# EL1034v4.net
KiCad netlist of a schematic drawn in EAGLE
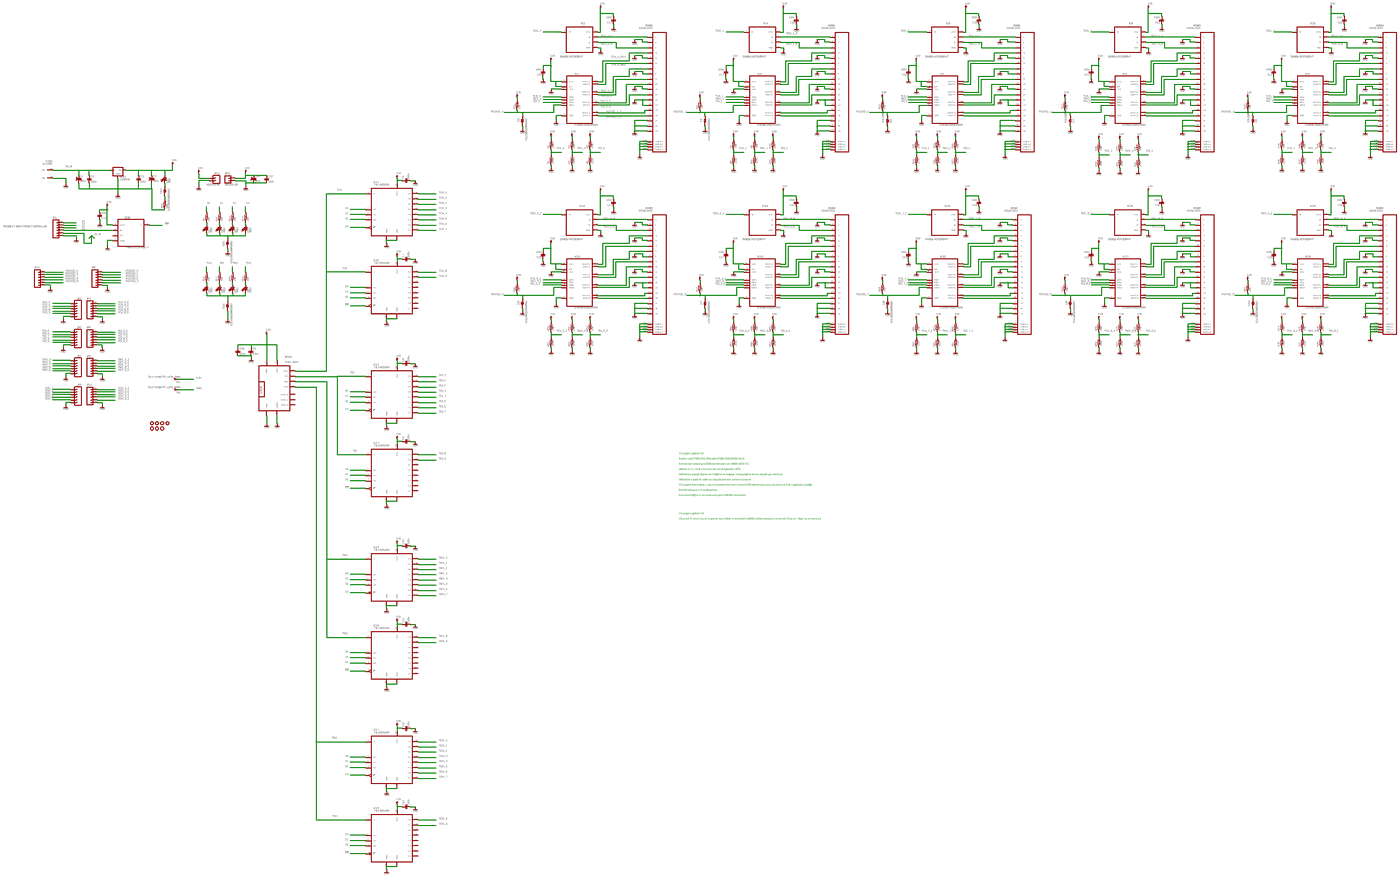
[diagram p0: schematic, sheet 1, overview]
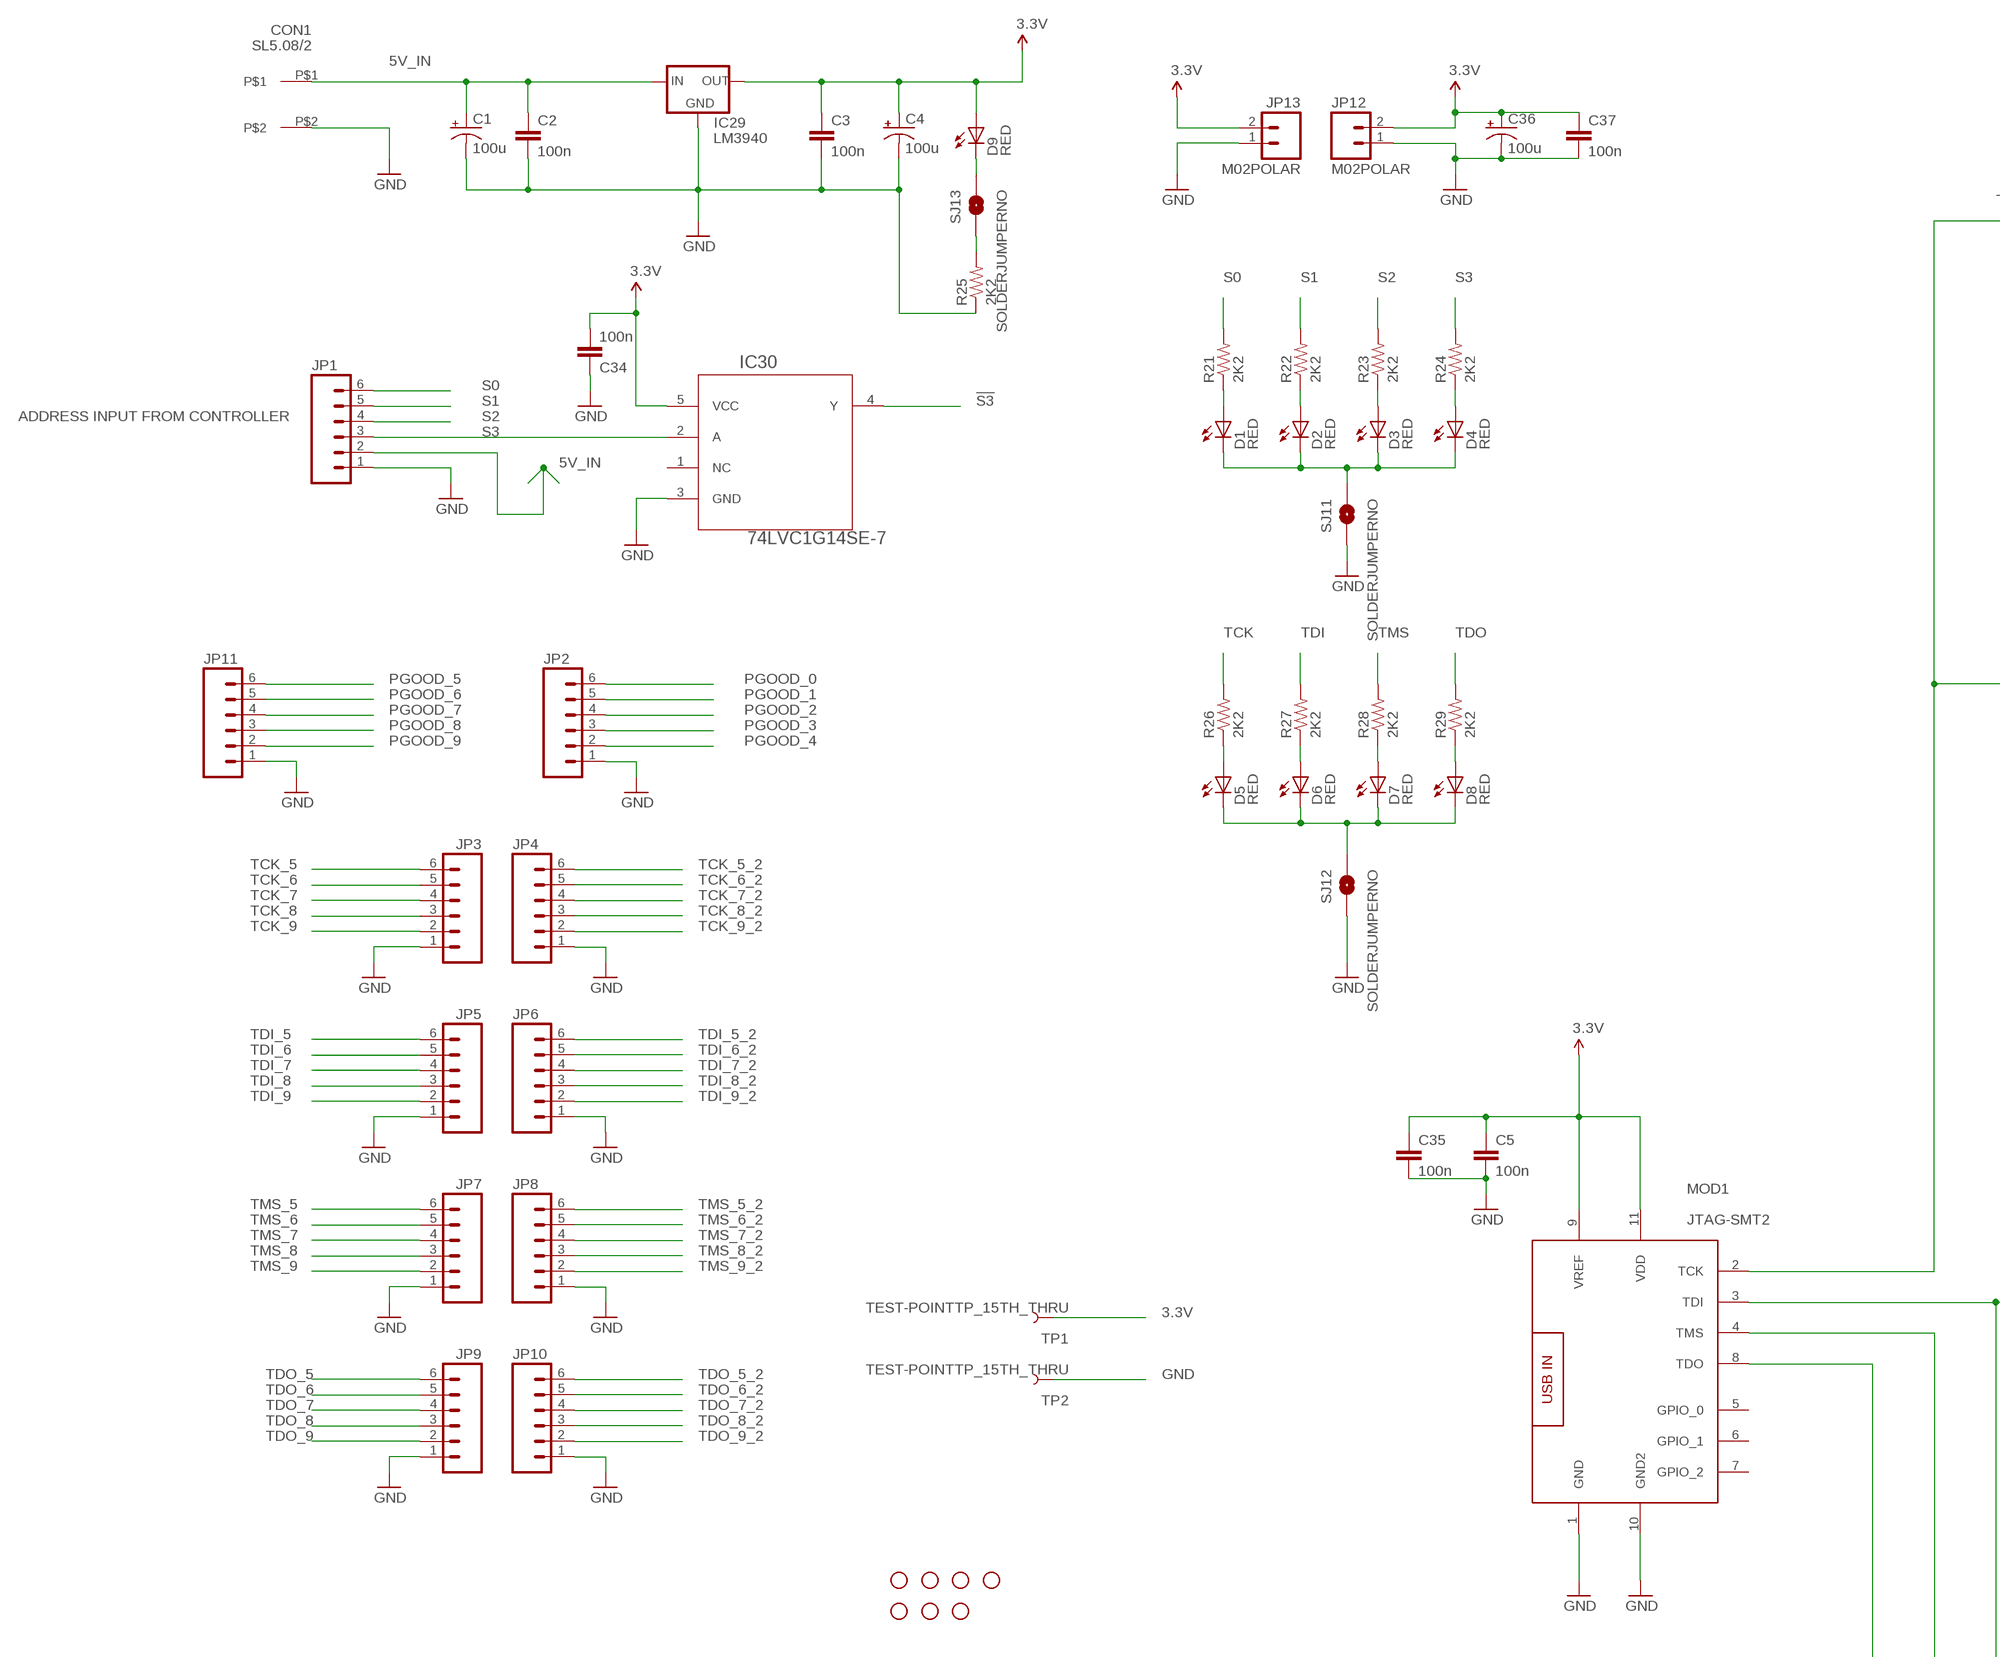
[diagram p1: schematic, sheet 1, part 1 of 6]
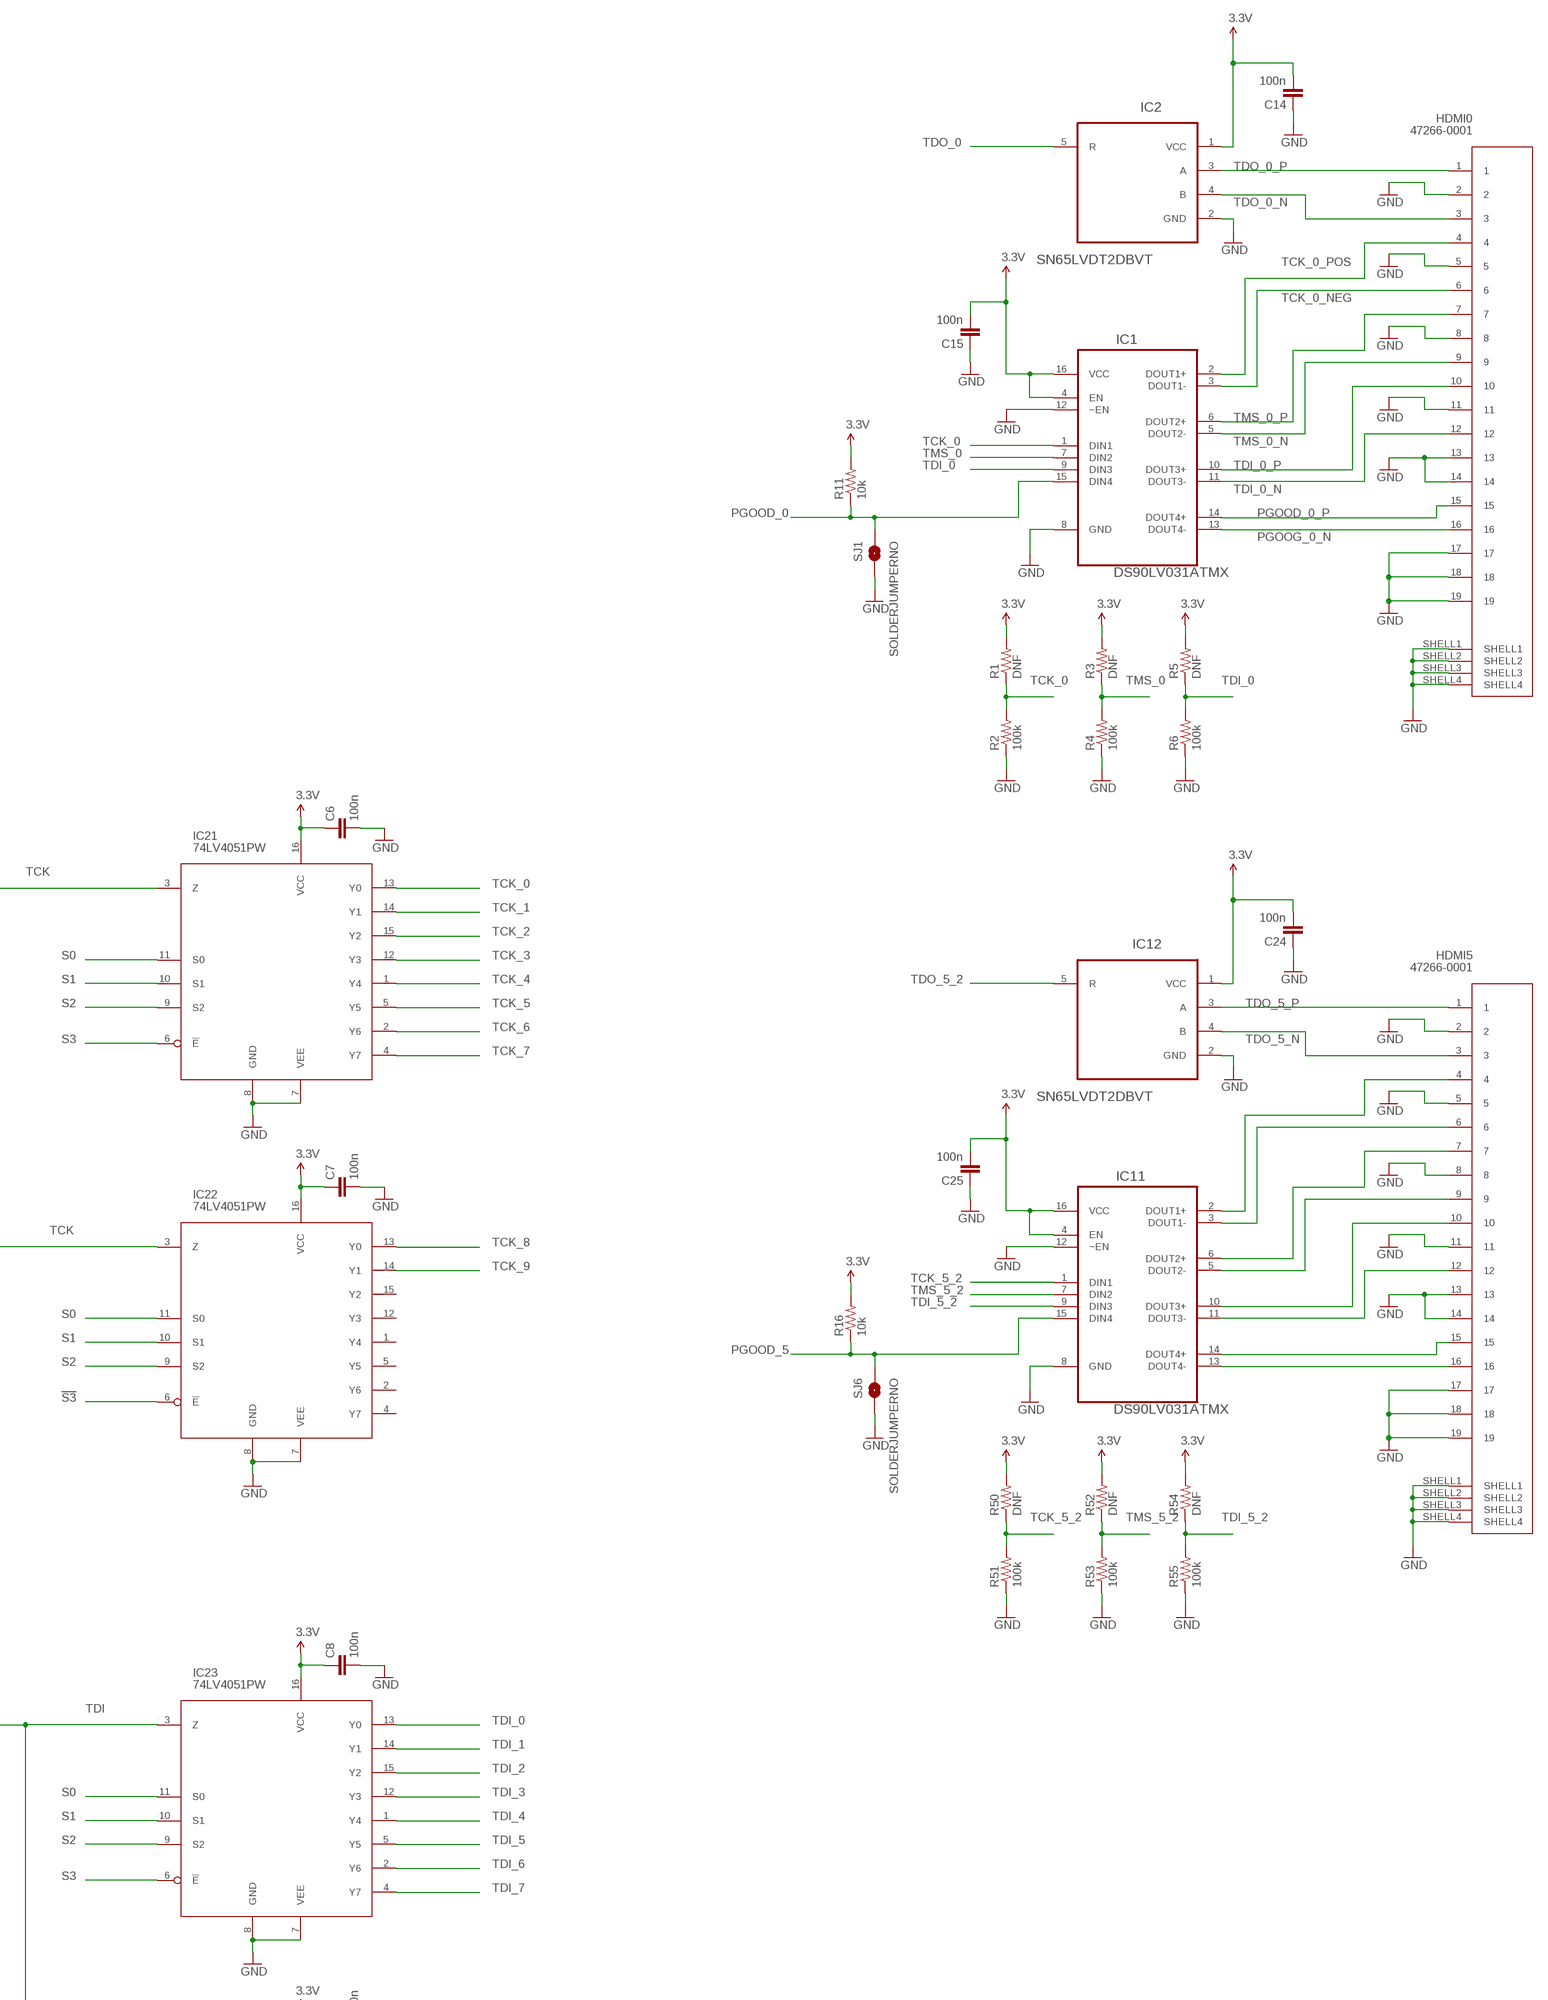
[diagram p2: schematic, sheet 1, part 2 of 6]
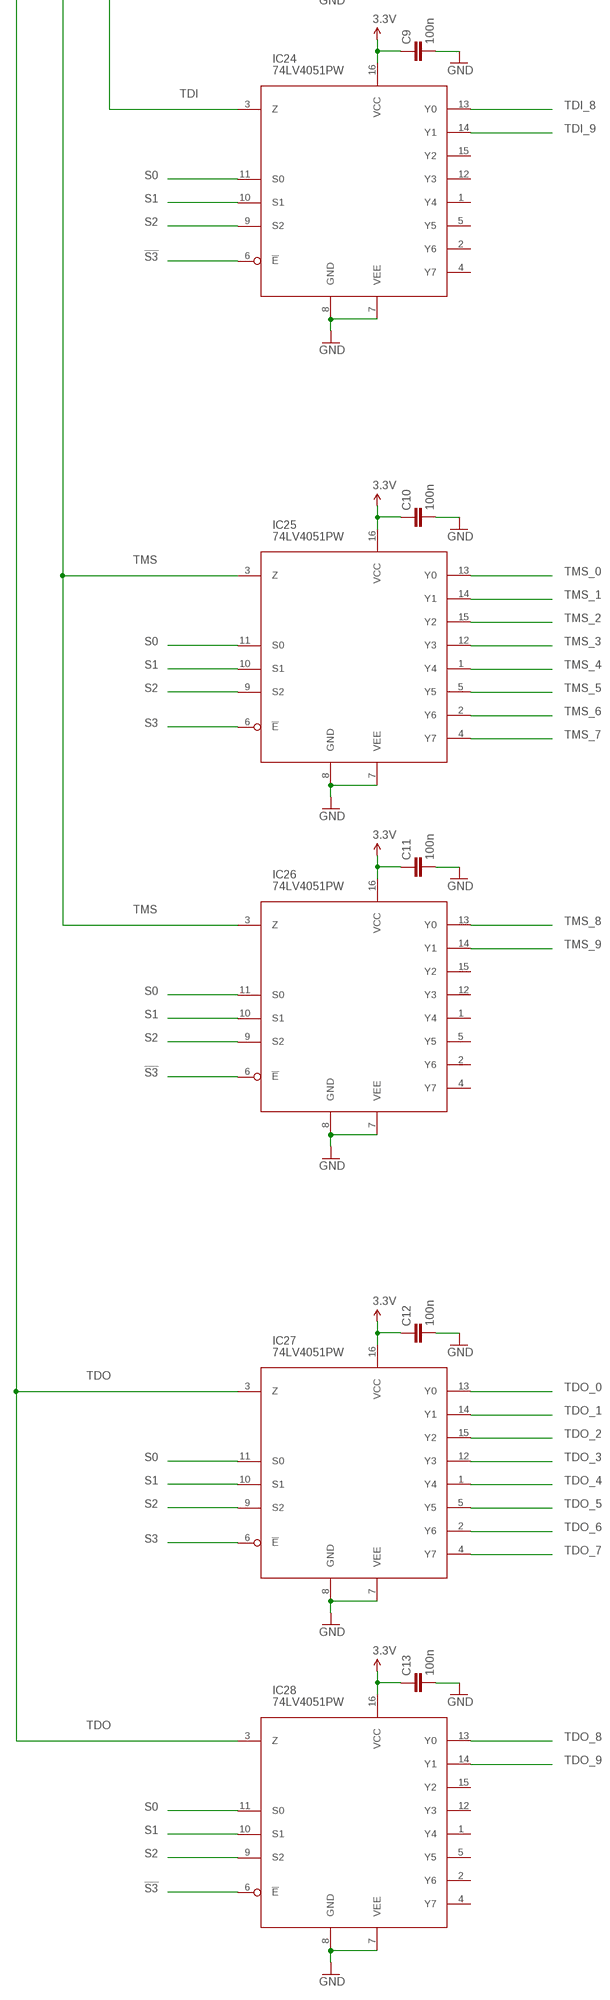
[diagram p3: schematic, sheet 1, part 3 of 6]
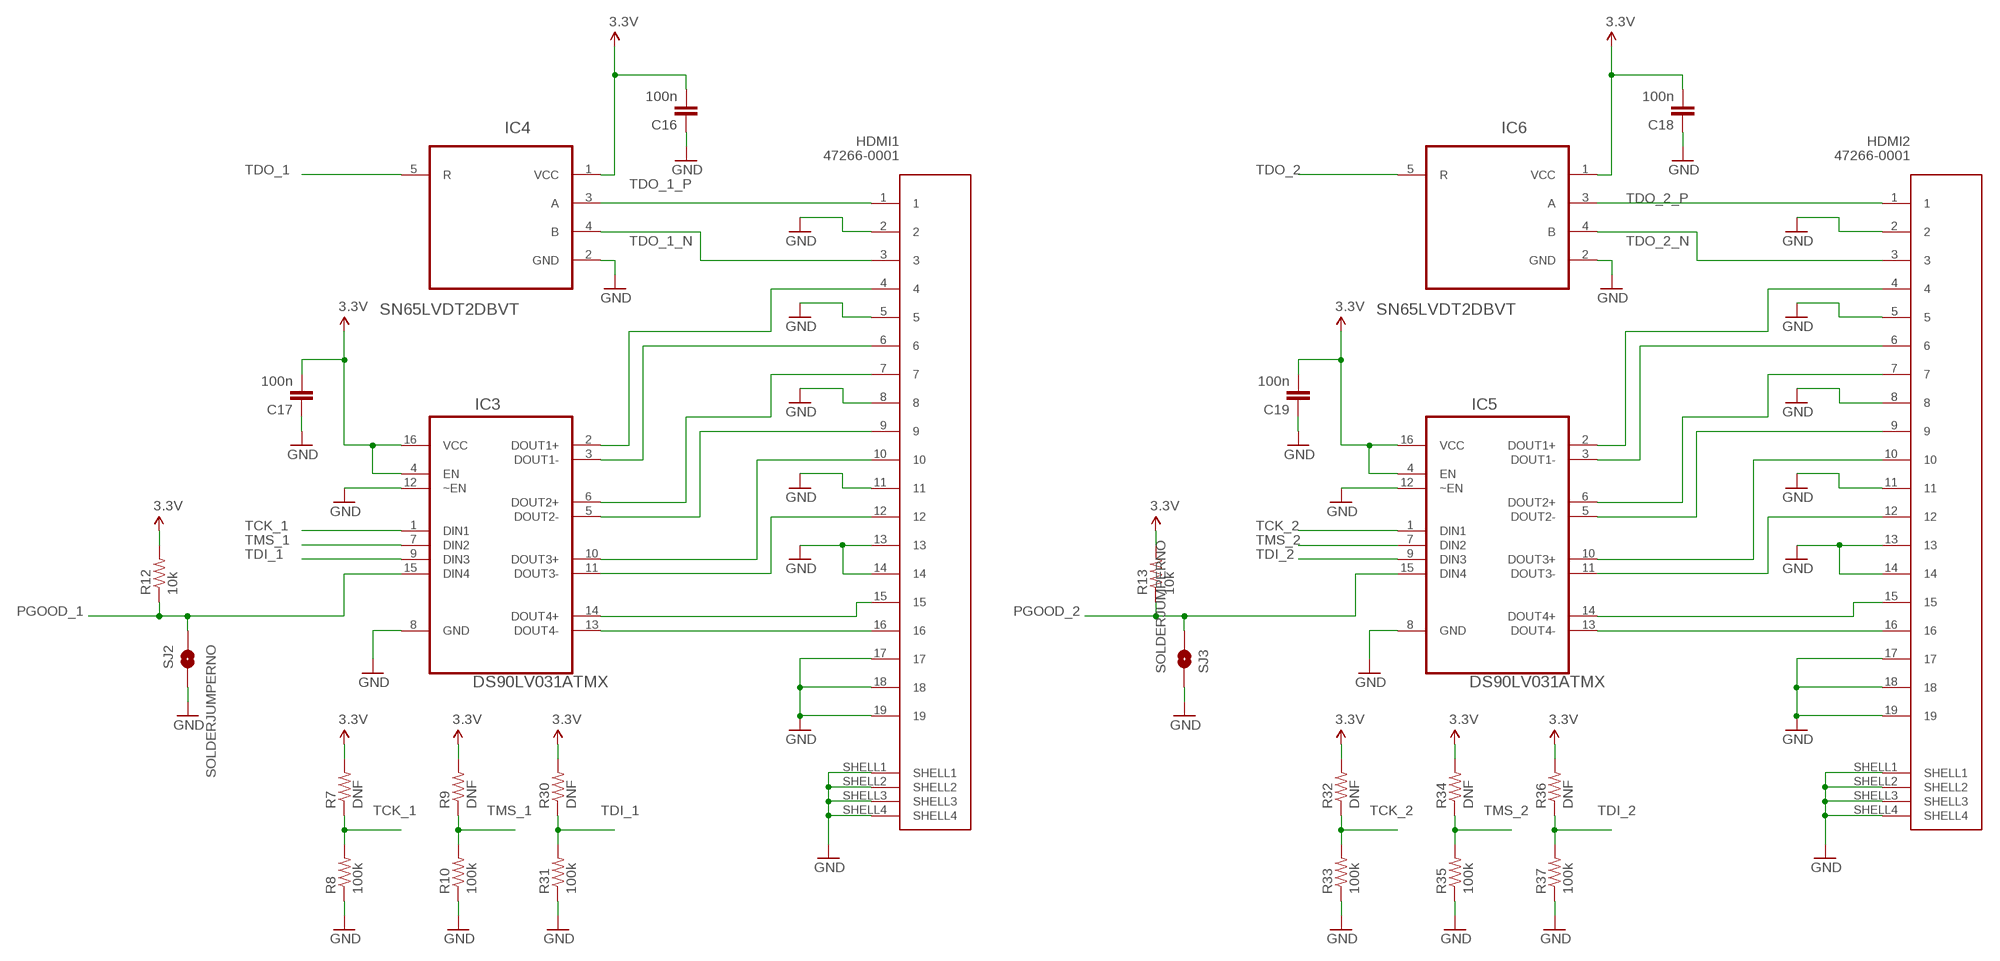
[diagram p4: schematic, sheet 1, part 4 of 6]
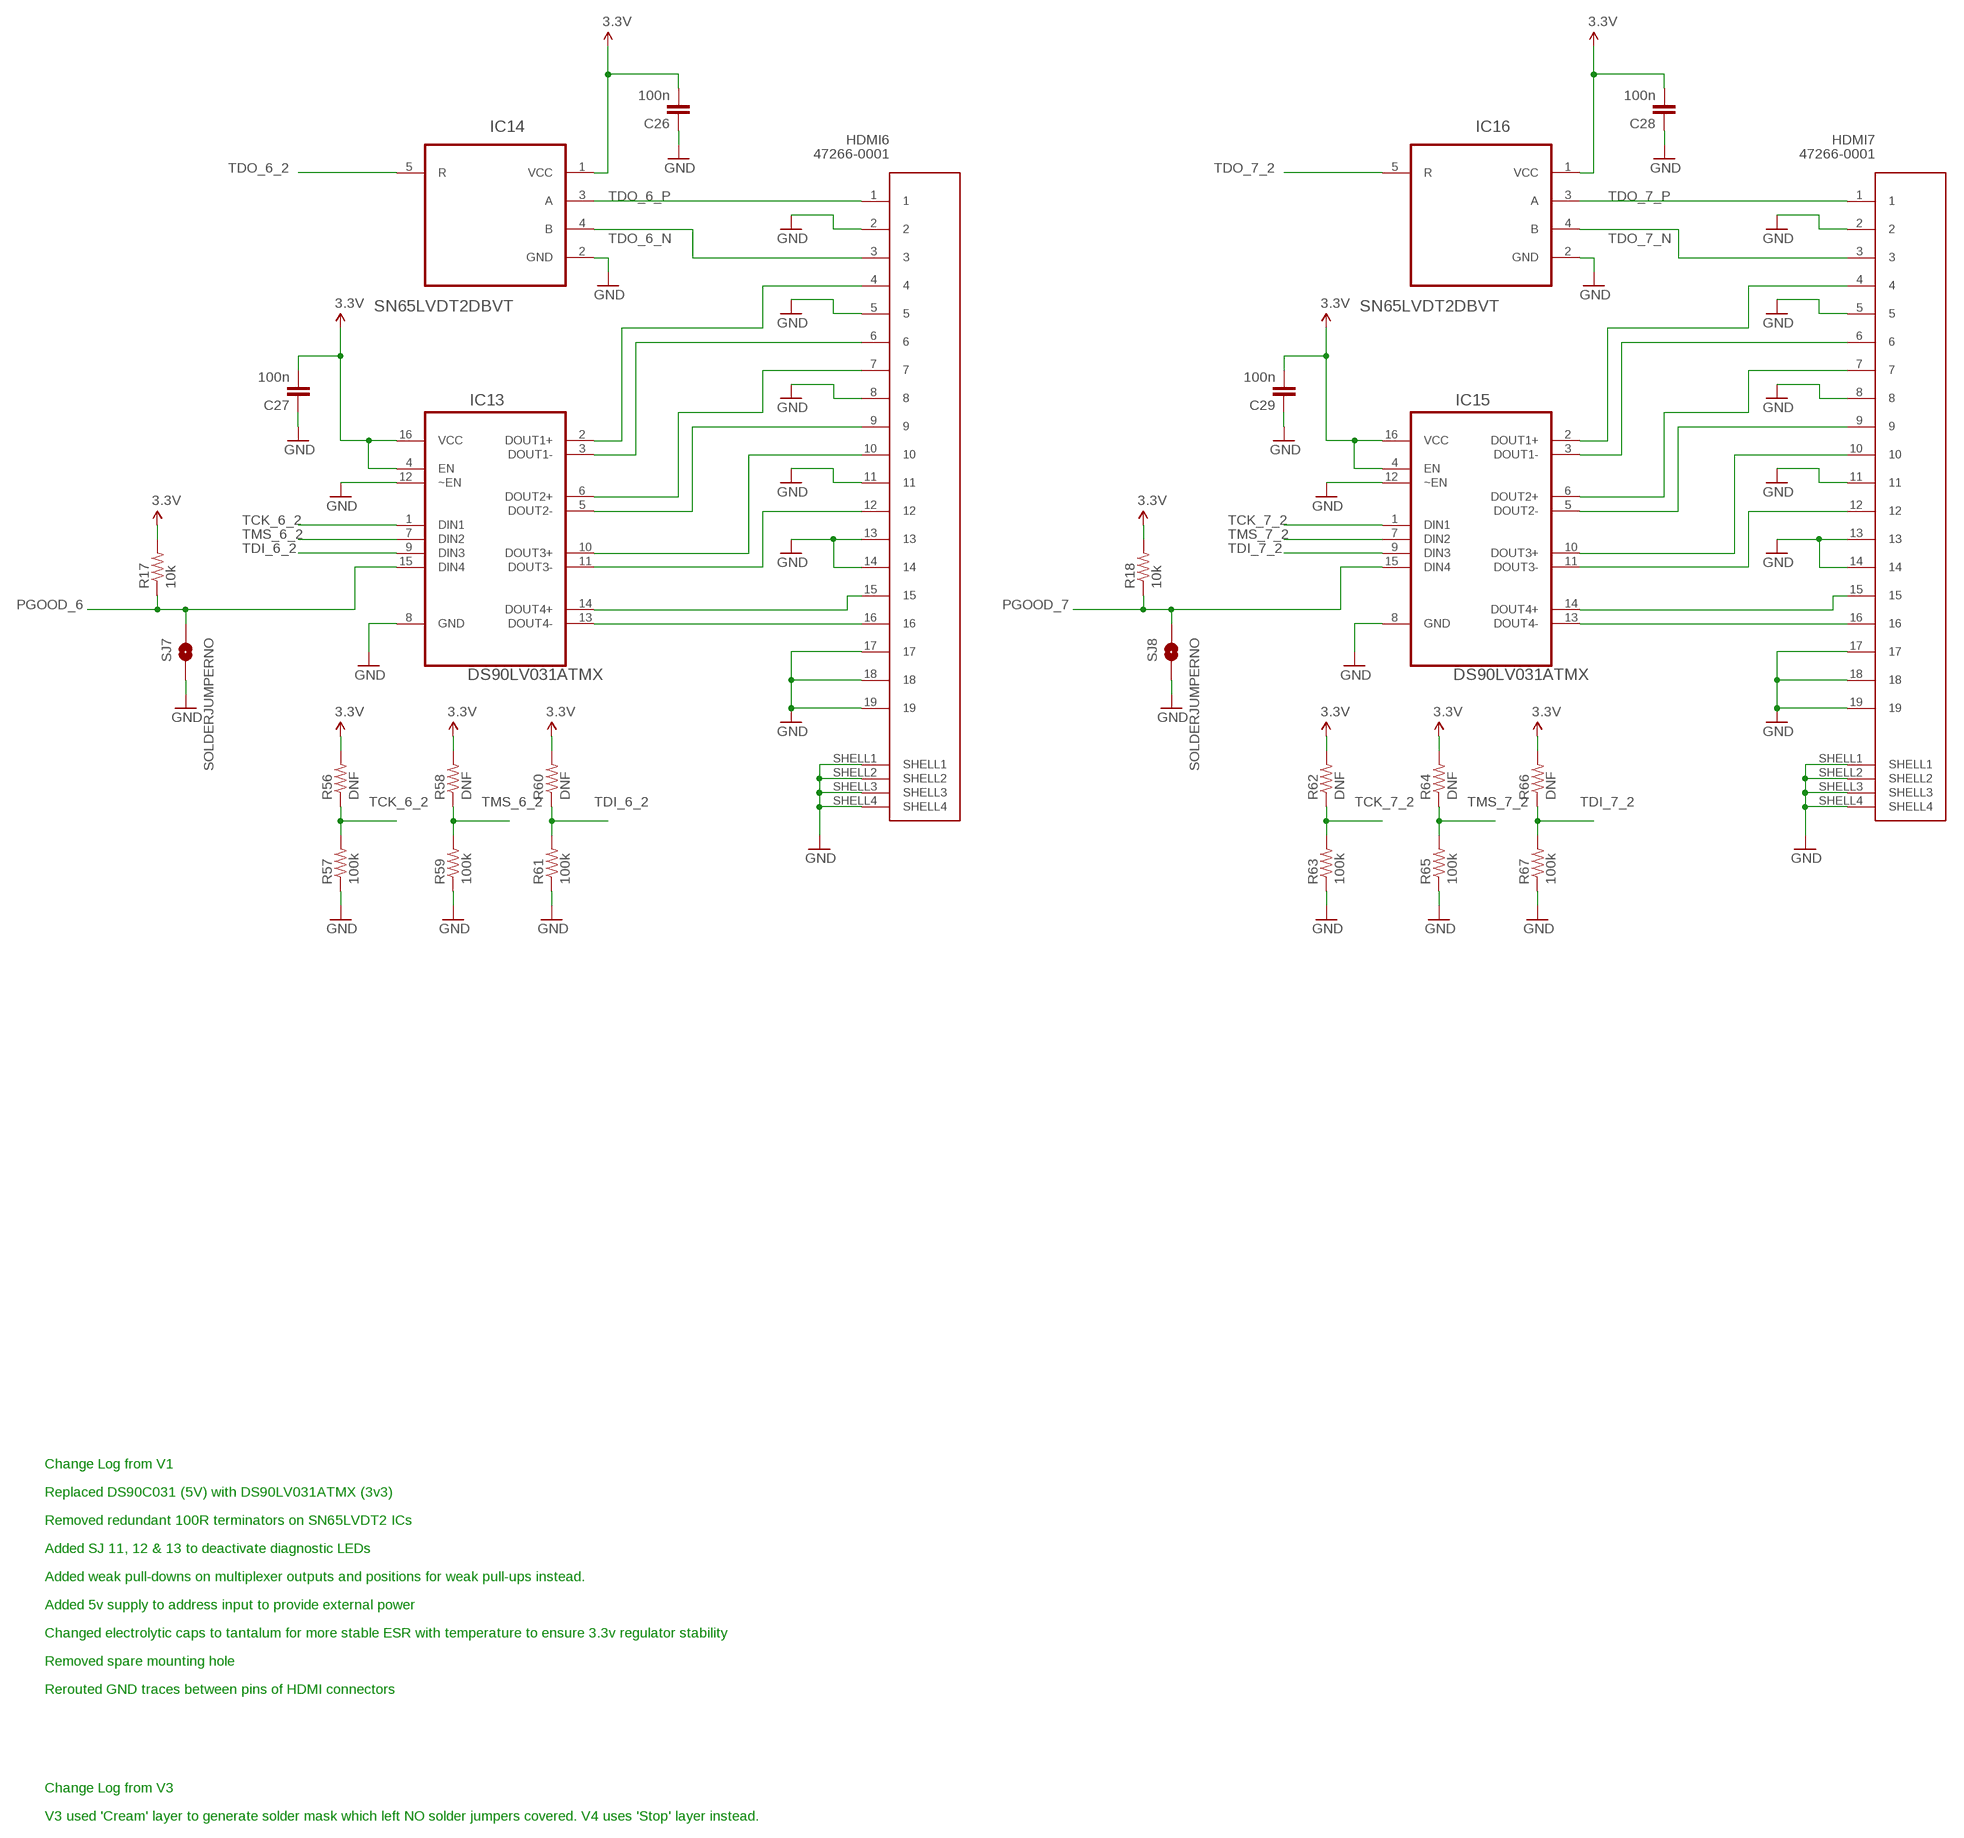
[diagram p5: schematic, sheet 1, part 5 of 6]
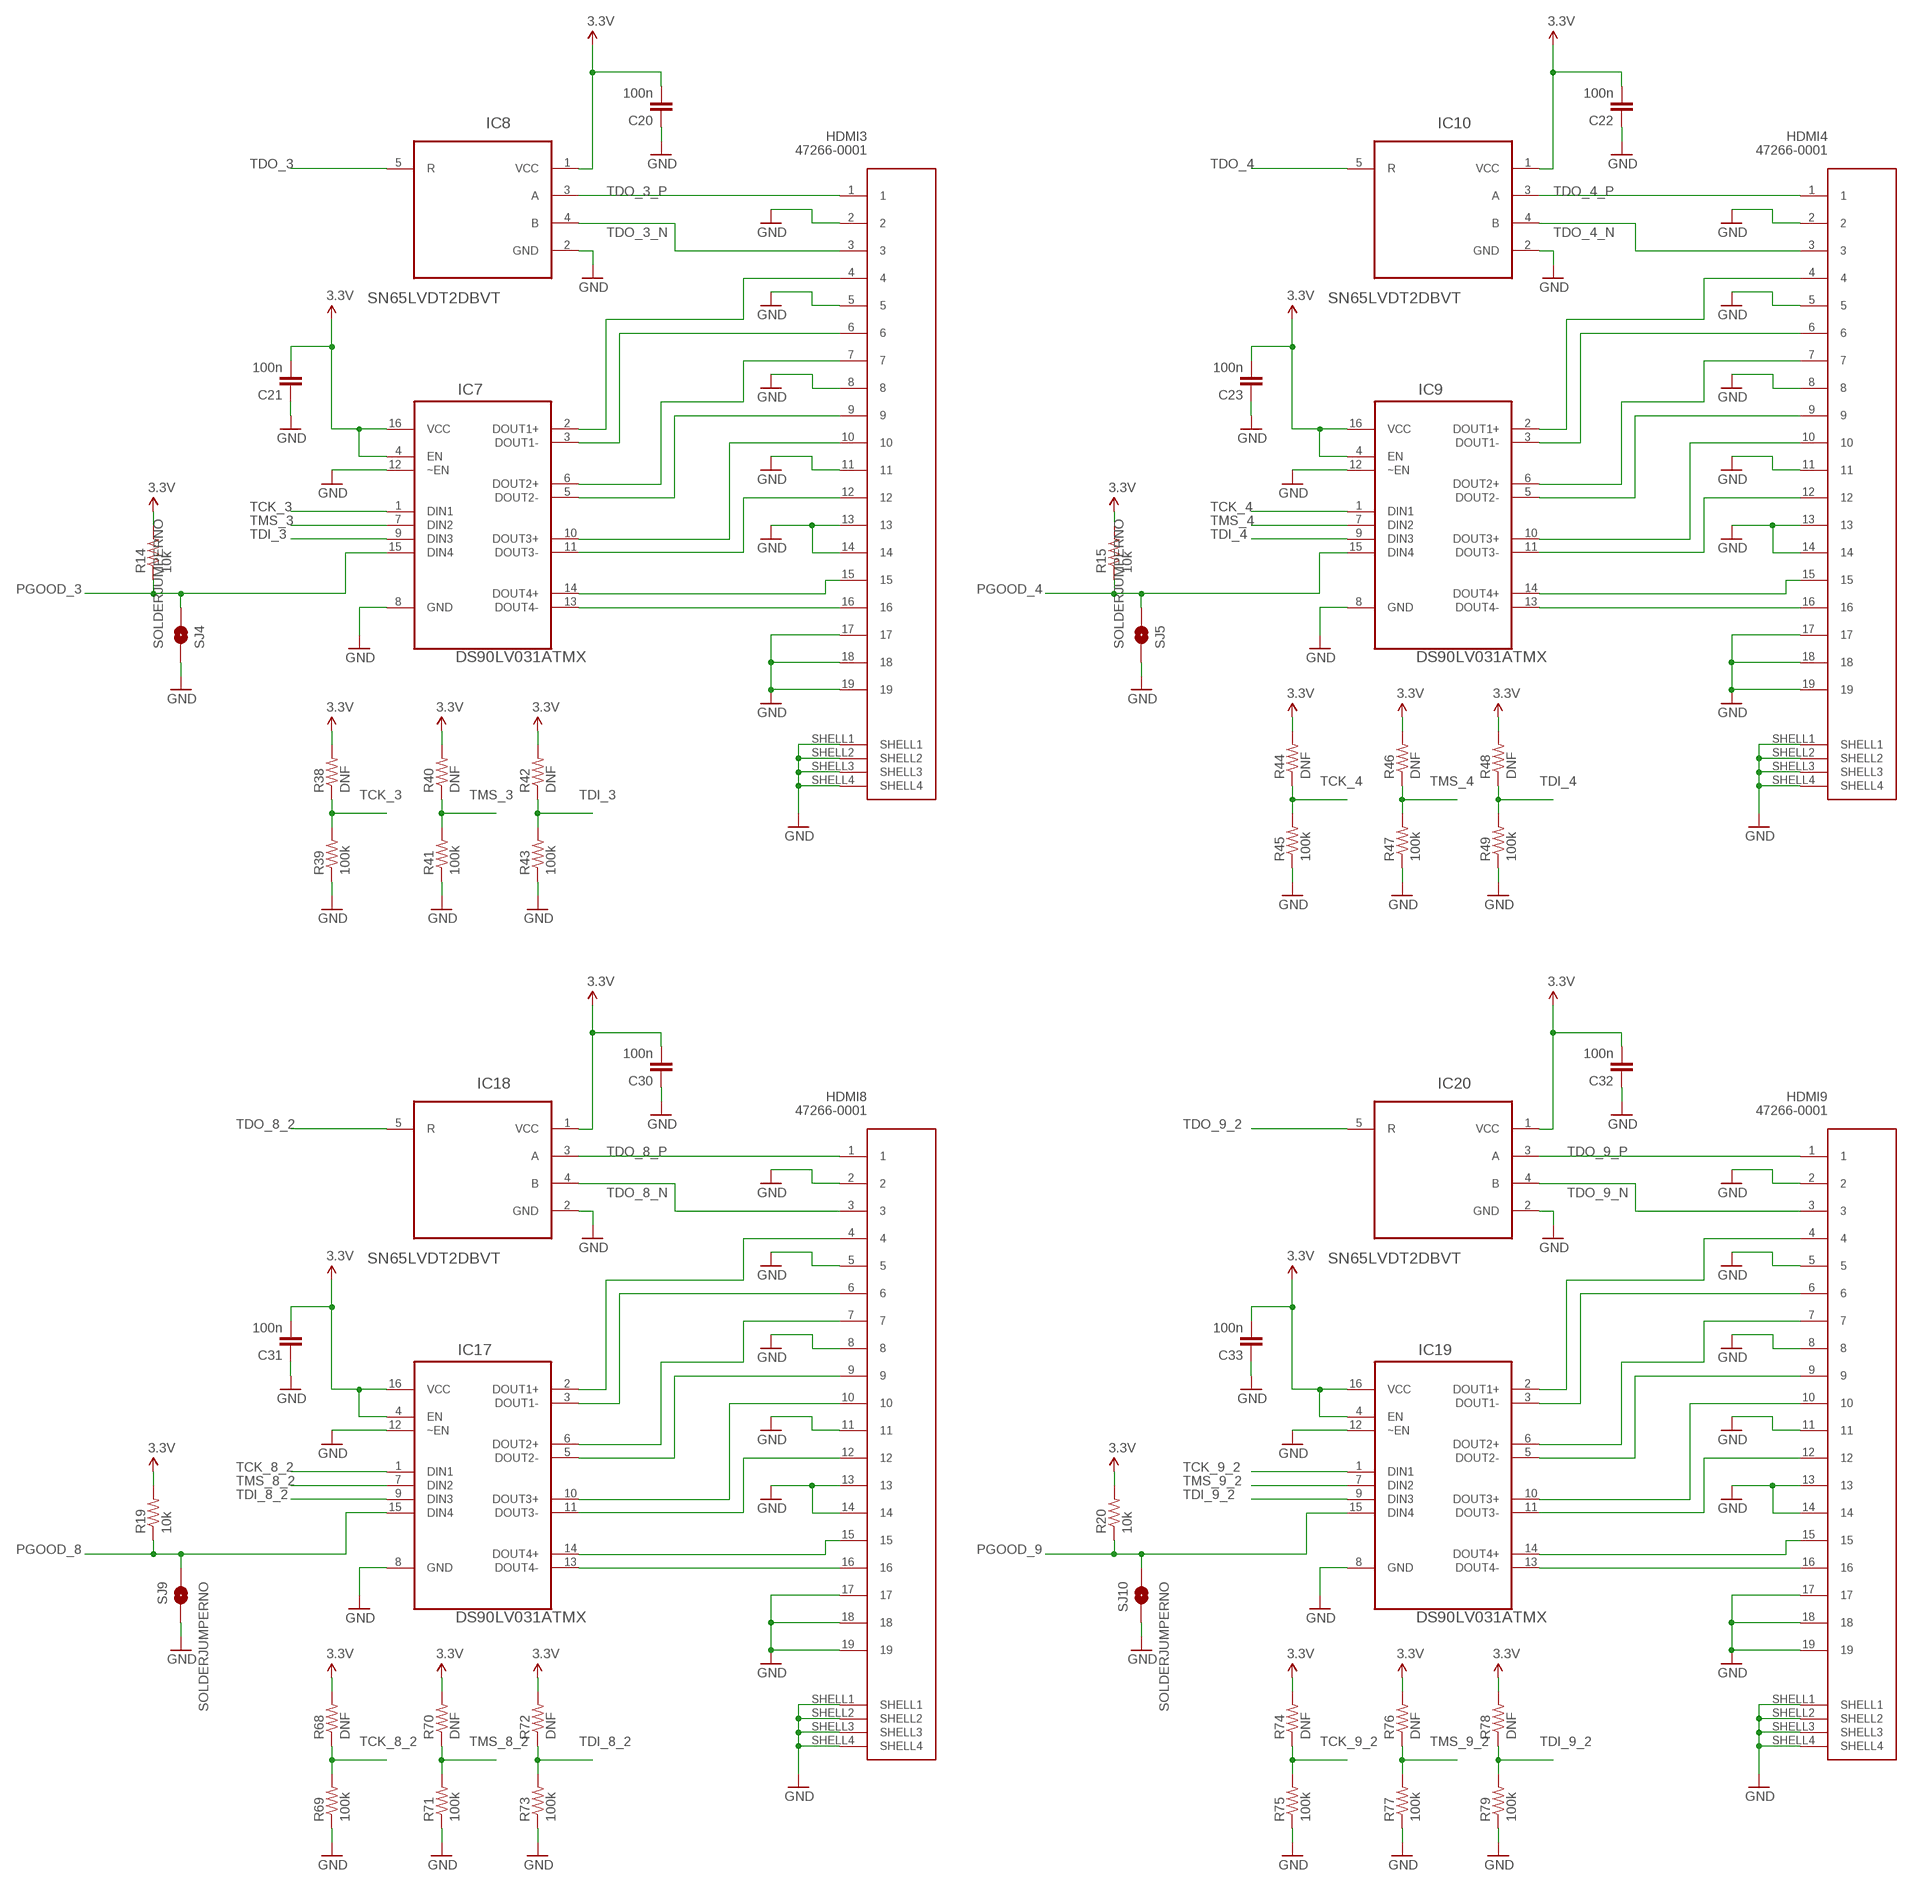
[diagram p6: schematic, sheet 1, part 6 of 6]

(export (version "E")
  (design (tool "Eeschema 10.0.6"))
  (components
    (comp (ref "C1")
      (value "100u")
      (footprint "eagle-import:EIA7343")
      (libsource (lib "eagle-import") (part "CAP_POL7343"))
    )
    (comp (ref "C2")
      (value "100n")
      (footprint "eagle-import:0805")
      (libsource (lib "eagle-import") (part "CAP0805"))
    )
    (comp (ref "C3")
      (value "100n")
      (footprint "eagle-import:0805")
      (libsource (lib "eagle-import") (part "CAP0805"))
    )
    (comp (ref "C4")
      (value "100u")
      (footprint "eagle-import:EIA7343")
      (libsource (lib "eagle-import") (part "CAP_POL7343"))
    )
    (comp (ref "C5")
      (value "100n")
      (footprint "eagle-import:0805")
      (libsource (lib "eagle-import") (part "CAP0805"))
    )
    (comp (ref "C6")
      (value "100n")
      (footprint "eagle-import:0805")
      (libsource (lib "eagle-import") (part "CAP0805"))
    )
    (comp (ref "C7")
      (value "100n")
      (footprint "eagle-import:0805")
      (libsource (lib "eagle-import") (part "CAP0805"))
    )
    (comp (ref "C8")
      (value "100n")
      (footprint "eagle-import:0805")
      (libsource (lib "eagle-import") (part "CAP0805"))
    )
    (comp (ref "C9")
      (value "100n")
      (footprint "eagle-import:0805")
      (libsource (lib "eagle-import") (part "CAP0805"))
    )
    (comp (ref "C10")
      (value "100n")
      (footprint "eagle-import:0805")
      (libsource (lib "eagle-import") (part "CAP0805"))
    )
    (comp (ref "C11")
      (value "100n")
      (footprint "eagle-import:0805")
      (libsource (lib "eagle-import") (part "CAP0805"))
    )
    (comp (ref "C12")
      (value "100n")
      (footprint "eagle-import:0805")
      (libsource (lib "eagle-import") (part "CAP0805"))
    )
    (comp (ref "C13")
      (value "100n")
      (footprint "eagle-import:0805")
      (libsource (lib "eagle-import") (part "CAP0805"))
    )
    (comp (ref "C14")
      (value "100n")
      (footprint "eagle-import:0805")
      (libsource (lib "eagle-import") (part "CAP0805"))
    )
    (comp (ref "C15")
      (value "100n")
      (footprint "eagle-import:0805")
      (libsource (lib "eagle-import") (part "CAP0805"))
    )
    (comp (ref "C16")
      (value "100n")
      (footprint "eagle-import:0805")
      (libsource (lib "eagle-import") (part "CAP0805"))
    )
    (comp (ref "C17")
      (value "100n")
      (footprint "eagle-import:0805")
      (libsource (lib "eagle-import") (part "CAP0805"))
    )
    (comp (ref "C18")
      (value "100n")
      (footprint "eagle-import:0805")
      (libsource (lib "eagle-import") (part "CAP0805"))
    )
    (comp (ref "C19")
      (value "100n")
      (footprint "eagle-import:0805")
      (libsource (lib "eagle-import") (part "CAP0805"))
    )
    (comp (ref "C20")
      (value "100n")
      (footprint "eagle-import:0805")
      (libsource (lib "eagle-import") (part "CAP0805"))
    )
    (comp (ref "C21")
      (value "100n")
      (footprint "eagle-import:0805")
      (libsource (lib "eagle-import") (part "CAP0805"))
    )
    (comp (ref "C22")
      (value "100n")
      (footprint "eagle-import:0805")
      (libsource (lib "eagle-import") (part "CAP0805"))
    )
    (comp (ref "C23")
      (value "100n")
      (footprint "eagle-import:0805")
      (libsource (lib "eagle-import") (part "CAP0805"))
    )
    (comp (ref "C24")
      (value "100n")
      (footprint "eagle-import:0805")
      (libsource (lib "eagle-import") (part "CAP0805"))
    )
    (comp (ref "C25")
      (value "100n")
      (footprint "eagle-import:0805")
      (libsource (lib "eagle-import") (part "CAP0805"))
    )
    (comp (ref "C26")
      (value "100n")
      (footprint "eagle-import:0805")
      (libsource (lib "eagle-import") (part "CAP0805"))
    )
    (comp (ref "C27")
      (value "100n")
      (footprint "eagle-import:0805")
      (libsource (lib "eagle-import") (part "CAP0805"))
    )
    (comp (ref "C28")
      (value "100n")
      (footprint "eagle-import:0805")
      (libsource (lib "eagle-import") (part "CAP0805"))
    )
    (comp (ref "C29")
      (value "100n")
      (footprint "eagle-import:0805")
      (libsource (lib "eagle-import") (part "CAP0805"))
    )
    (comp (ref "C30")
      (value "100n")
      (footprint "eagle-import:0805")
      (libsource (lib "eagle-import") (part "CAP0805"))
    )
    (comp (ref "C31")
      (value "100n")
      (footprint "eagle-import:0805")
      (libsource (lib "eagle-import") (part "CAP0805"))
    )
    (comp (ref "C32")
      (value "100n")
      (footprint "eagle-import:0805")
      (libsource (lib "eagle-import") (part "CAP0805"))
    )
    (comp (ref "C33")
      (value "100n")
      (footprint "eagle-import:0805")
      (libsource (lib "eagle-import") (part "CAP0805"))
    )
    (comp (ref "C34")
      (value "100n")
      (footprint "eagle-import:0805")
      (libsource (lib "eagle-import") (part "CAP0805"))
    )
    (comp (ref "C35")
      (value "100n")
      (footprint "eagle-import:0805")
      (libsource (lib "eagle-import") (part "CAP0805"))
    )
    (comp (ref "C36")
      (value "100u")
      (footprint "eagle-import:EIA7343")
      (libsource (lib "eagle-import") (part "CAP_POL7343"))
    )
    (comp (ref "C37")
      (value "100n")
      (footprint "eagle-import:0805")
      (libsource (lib "eagle-import") (part "CAP0805"))
    )
    (comp (ref "CON1")
      (value "SL5.08/2")
      (footprint "eagle-import:SL5.08_2")
      (libsource (lib "eagle-import") (part "SL5.08/2"))
    )
    (comp (ref "D1")
      (value "RED")
      (footprint "eagle-import:LED-0603")
      (libsource (lib "eagle-import") (part "LED-RED0603"))
    )
    (comp (ref "D2")
      (value "RED")
      (footprint "eagle-import:LED-0603")
      (libsource (lib "eagle-import") (part "LED-RED0603"))
    )
    (comp (ref "D3")
      (value "RED")
      (footprint "eagle-import:LED-0603")
      (libsource (lib "eagle-import") (part "LED-RED0603"))
    )
    (comp (ref "D4")
      (value "RED")
      (footprint "eagle-import:LED-0603")
      (libsource (lib "eagle-import") (part "LED-RED0603"))
    )
    (comp (ref "D5")
      (value "RED")
      (footprint "eagle-import:LED-0603")
      (libsource (lib "eagle-import") (part "LED-RED0603"))
    )
    (comp (ref "D6")
      (value "RED")
      (footprint "eagle-import:LED-0603")
      (libsource (lib "eagle-import") (part "LED-RED0603"))
    )
    (comp (ref "D7")
      (value "RED")
      (footprint "eagle-import:LED-0603")
      (libsource (lib "eagle-import") (part "LED-RED0603"))
    )
    (comp (ref "D8")
      (value "RED")
      (footprint "eagle-import:LED-0603")
      (libsource (lib "eagle-import") (part "LED-RED0603"))
    )
    (comp (ref "D9")
      (value "RED")
      (footprint "eagle-import:LED-0603")
      (libsource (lib "eagle-import") (part "LED-RED0603"))
    )
    (comp (ref "HDMI0")
      (value "47266-0001")
      (footprint "eagle-import:47266-0001")
      (libsource (lib "eagle-import") (part "47266-0001"))
    )
    (comp (ref "HDMI1")
      (value "47266-0001")
      (footprint "eagle-import:47266-0001")
      (libsource (lib "eagle-import") (part "47266-0001"))
    )
    (comp (ref "HDMI2")
      (value "47266-0001")
      (footprint "eagle-import:47266-0001")
      (libsource (lib "eagle-import") (part "47266-0001"))
    )
    (comp (ref "HDMI3")
      (value "47266-0001")
      (footprint "eagle-import:47266-0001")
      (libsource (lib "eagle-import") (part "47266-0001"))
    )
    (comp (ref "HDMI4")
      (value "47266-0001")
      (footprint "eagle-import:47266-0001")
      (libsource (lib "eagle-import") (part "47266-0001"))
    )
    (comp (ref "HDMI5")
      (value "47266-0001")
      (footprint "eagle-import:47266-0001")
      (libsource (lib "eagle-import") (part "47266-0001"))
    )
    (comp (ref "HDMI6")
      (value "47266-0001")
      (footprint "eagle-import:47266-0001")
      (libsource (lib "eagle-import") (part "47266-0001"))
    )
    (comp (ref "HDMI7")
      (value "47266-0001")
      (footprint "eagle-import:47266-0001")
      (libsource (lib "eagle-import") (part "47266-0001"))
    )
    (comp (ref "HDMI8")
      (value "47266-0001")
      (footprint "eagle-import:47266-0001")
      (libsource (lib "eagle-import") (part "47266-0001"))
    )
    (comp (ref "HDMI9")
      (value "47266-0001")
      (footprint "eagle-import:47266-0001")
      (libsource (lib "eagle-import") (part "47266-0001"))
    )
    (comp (ref "IC1")
      (value "DS90LV031ATMX")
      (footprint "eagle-import:SOIC127P600X175-16N")
      (fields (field (name "MPN") "DS90C031TM"))
      (libsource (lib "eagle-import") (part "DS90C031TM"))
    )
    (comp (ref "IC2")
      (value "SN65LVDT2DBVT")
      (footprint "eagle-import:SOT95P280X145-5N")
      (libsource (lib "eagle-import") (part "SN65LVDT2DBVT"))
    )
    (comp (ref "IC3")
      (value "DS90LV031ATMX")
      (footprint "eagle-import:SOIC127P600X175-16N")
      (fields (field (name "MPN") "DS90C031TM"))
      (libsource (lib "eagle-import") (part "DS90C031TM"))
    )
    (comp (ref "IC4")
      (value "SN65LVDT2DBVT")
      (footprint "eagle-import:SOT95P280X145-5N")
      (libsource (lib "eagle-import") (part "SN65LVDT2DBVT"))
    )
    (comp (ref "IC5")
      (value "DS90LV031ATMX")
      (footprint "eagle-import:SOIC127P600X175-16N")
      (fields (field (name "MPN") "DS90C031TM"))
      (libsource (lib "eagle-import") (part "DS90C031TM"))
    )
    (comp (ref "IC6")
      (value "SN65LVDT2DBVT")
      (footprint "eagle-import:SOT95P280X145-5N")
      (libsource (lib "eagle-import") (part "SN65LVDT2DBVT"))
    )
    (comp (ref "IC7")
      (value "DS90LV031ATMX")
      (footprint "eagle-import:SOIC127P600X175-16N")
      (fields (field (name "MPN") "DS90C031TM"))
      (libsource (lib "eagle-import") (part "DS90C031TM"))
    )
    (comp (ref "IC8")
      (value "SN65LVDT2DBVT")
      (footprint "eagle-import:SOT95P280X145-5N")
      (libsource (lib "eagle-import") (part "SN65LVDT2DBVT"))
    )
    (comp (ref "IC9")
      (value "DS90LV031ATMX")
      (footprint "eagle-import:SOIC127P600X175-16N")
      (fields (field (name "MPN") "DS90C031TM"))
      (libsource (lib "eagle-import") (part "DS90C031TM"))
    )
    (comp (ref "IC10")
      (value "SN65LVDT2DBVT")
      (footprint "eagle-import:SOT95P280X145-5N")
      (libsource (lib "eagle-import") (part "SN65LVDT2DBVT"))
    )
    (comp (ref "IC11")
      (value "DS90LV031ATMX")
      (footprint "eagle-import:SOIC127P600X175-16N")
      (fields (field (name "MPN") "DS90C031TM"))
      (libsource (lib "eagle-import") (part "DS90C031TM"))
    )
    (comp (ref "IC12")
      (value "SN65LVDT2DBVT")
      (footprint "eagle-import:SOT95P280X145-5N")
      (libsource (lib "eagle-import") (part "SN65LVDT2DBVT"))
    )
    (comp (ref "IC13")
      (value "DS90LV031ATMX")
      (footprint "eagle-import:SOIC127P600X175-16N")
      (fields (field (name "MPN") "DS90C031TM"))
      (libsource (lib "eagle-import") (part "DS90C031TM"))
    )
    (comp (ref "IC14")
      (value "SN65LVDT2DBVT")
      (footprint "eagle-import:SOT95P280X145-5N")
      (libsource (lib "eagle-import") (part "SN65LVDT2DBVT"))
    )
    (comp (ref "IC15")
      (value "DS90LV031ATMX")
      (footprint "eagle-import:SOIC127P600X175-16N")
      (fields (field (name "MPN") "DS90C031TM"))
      (libsource (lib "eagle-import") (part "DS90C031TM"))
    )
    (comp (ref "IC16")
      (value "SN65LVDT2DBVT")
      (footprint "eagle-import:SOT95P280X145-5N")
      (libsource (lib "eagle-import") (part "SN65LVDT2DBVT"))
    )
    (comp (ref "IC17")
      (value "DS90LV031ATMX")
      (footprint "eagle-import:SOIC127P600X175-16N")
      (fields (field (name "MPN") "DS90C031TM"))
      (libsource (lib "eagle-import") (part "DS90C031TM"))
    )
    (comp (ref "IC18")
      (value "SN65LVDT2DBVT")
      (footprint "eagle-import:SOT95P280X145-5N")
      (libsource (lib "eagle-import") (part "SN65LVDT2DBVT"))
    )
    (comp (ref "IC19")
      (value "DS90LV031ATMX")
      (footprint "eagle-import:SOIC127P600X175-16N")
      (fields (field (name "MPN") "DS90C031TM"))
      (libsource (lib "eagle-import") (part "DS90C031TM"))
    )
    (comp (ref "IC20")
      (value "SN65LVDT2DBVT")
      (footprint "eagle-import:SOT95P280X145-5N")
      (libsource (lib "eagle-import") (part "SN65LVDT2DBVT"))
    )
    (comp (ref "IC21")
      (value "74LV4051PW")
      (footprint "eagle-import:TSSOP16")
      (libsource (lib "eagle-import") (part "74LV4051PW"))
    )
    (comp (ref "IC22")
      (value "74LV4051PW")
      (footprint "eagle-import:TSSOP16")
      (libsource (lib "eagle-import") (part "74LV4051PW"))
    )
    (comp (ref "IC23")
      (value "74LV4051PW")
      (footprint "eagle-import:TSSOP16")
      (libsource (lib "eagle-import") (part "74LV4051PW"))
    )
    (comp (ref "IC24")
      (value "74LV4051PW")
      (footprint "eagle-import:TSSOP16")
      (libsource (lib "eagle-import") (part "74LV4051PW"))
    )
    (comp (ref "IC25")
      (value "74LV4051PW")
      (footprint "eagle-import:TSSOP16")
      (libsource (lib "eagle-import") (part "74LV4051PW"))
    )
    (comp (ref "IC26")
      (value "74LV4051PW")
      (footprint "eagle-import:TSSOP16")
      (libsource (lib "eagle-import") (part "74LV4051PW"))
    )
    (comp (ref "IC27")
      (value "74LV4051PW")
      (footprint "eagle-import:TSSOP16")
      (libsource (lib "eagle-import") (part "74LV4051PW"))
    )
    (comp (ref "IC28")
      (value "74LV4051PW")
      (footprint "eagle-import:TSSOP16")
      (libsource (lib "eagle-import") (part "74LV4051PW"))
    )
    (comp (ref "IC29")
      (value "LM3940")
      (footprint "eagle-import:TO220-IGO")
      (libsource (lib "eagle-import") (part "V_REG_78XXSINK"))
    )
    (comp (ref "IC30")
      (value "74LVC1G14SE-7")
      (footprint "eagle-import:SOT65P210X110-5N")
      (libsource (lib "eagle-import") (part "74LVC1G14SE-7"))
    )
    (comp (ref "JP1")
      (value "M06POLAR")
      (footprint "eagle-import:MOLEX-1X6")
      (libsource (lib "eagle-import") (part "M06POLAR"))
    )
    (comp (ref "JP2")
      (value "M06POLAR")
      (footprint "eagle-import:MOLEX-1X6")
      (libsource (lib "eagle-import") (part "M06POLAR"))
    )
    (comp (ref "JP3")
      (value "M06POLAR")
      (footprint "eagle-import:MOLEX-1X6")
      (libsource (lib "eagle-import") (part "M06POLAR"))
    )
    (comp (ref "JP4")
      (value "M06POLAR")
      (footprint "eagle-import:MOLEX-1X6")
      (libsource (lib "eagle-import") (part "M06POLAR"))
    )
    (comp (ref "JP5")
      (value "M06POLAR")
      (footprint "eagle-import:MOLEX-1X6")
      (libsource (lib "eagle-import") (part "M06POLAR"))
    )
    (comp (ref "JP6")
      (value "M06POLAR")
      (footprint "eagle-import:MOLEX-1X6")
      (libsource (lib "eagle-import") (part "M06POLAR"))
    )
    (comp (ref "JP7")
      (value "M06POLAR")
      (footprint "eagle-import:MOLEX-1X6")
      (libsource (lib "eagle-import") (part "M06POLAR"))
    )
    (comp (ref "JP8")
      (value "M06POLAR")
      (footprint "eagle-import:MOLEX-1X6")
      (libsource (lib "eagle-import") (part "M06POLAR"))
    )
    (comp (ref "JP9")
      (value "M06POLAR")
      (footprint "eagle-import:MOLEX-1X6")
      (libsource (lib "eagle-import") (part "M06POLAR"))
    )
    (comp (ref "JP10")
      (value "M06POLAR")
      (footprint "eagle-import:MOLEX-1X6")
      (libsource (lib "eagle-import") (part "M06POLAR"))
    )
    (comp (ref "JP11")
      (value "M06POLAR")
      (footprint "eagle-import:MOLEX-1X6")
      (libsource (lib "eagle-import") (part "M06POLAR"))
    )
    (comp (ref "JP12")
      (value "M02POLAR")
      (footprint "eagle-import:MOLEX-1X2")
      (libsource (lib "eagle-import") (part "M02POLAR"))
    )
    (comp (ref "JP13")
      (value "M02POLAR")
      (footprint "eagle-import:MOLEX-1X2")
      (libsource (lib "eagle-import") (part "M02POLAR"))
    )
    (comp (ref "MOD1")
      (value "JTAG-SMT2")
      (footprint "eagle-import:JTAG_SMT2")
      (libsource (lib "eagle-import") (part "JTAG-SMT2"))
    )
    (comp (ref "R1")
      (value "DNF")
      (footprint "eagle-import:0603-RES")
      (libsource (lib "eagle-import") (part "RESISTOR0603-RES"))
    )
    (comp (ref "R2")
      (value "100k")
      (footprint "eagle-import:0603-RES")
      (libsource (lib "eagle-import") (part "RESISTOR0603-RES"))
    )
    (comp (ref "R3")
      (value "DNF")
      (footprint "eagle-import:0603-RES")
      (libsource (lib "eagle-import") (part "RESISTOR0603-RES"))
    )
    (comp (ref "R4")
      (value "100k")
      (footprint "eagle-import:0603-RES")
      (libsource (lib "eagle-import") (part "RESISTOR0603-RES"))
    )
    (comp (ref "R5")
      (value "DNF")
      (footprint "eagle-import:0603-RES")
      (libsource (lib "eagle-import") (part "RESISTOR0603-RES"))
    )
    (comp (ref "R6")
      (value "100k")
      (footprint "eagle-import:0603-RES")
      (libsource (lib "eagle-import") (part "RESISTOR0603-RES"))
    )
    (comp (ref "R7")
      (value "DNF")
      (footprint "eagle-import:0603-RES")
      (libsource (lib "eagle-import") (part "RESISTOR0603-RES"))
    )
    (comp (ref "R8")
      (value "100k")
      (footprint "eagle-import:0603-RES")
      (libsource (lib "eagle-import") (part "RESISTOR0603-RES"))
    )
    (comp (ref "R9")
      (value "DNF")
      (footprint "eagle-import:0603-RES")
      (libsource (lib "eagle-import") (part "RESISTOR0603-RES"))
    )
    (comp (ref "R10")
      (value "100k")
      (footprint "eagle-import:0603-RES")
      (libsource (lib "eagle-import") (part "RESISTOR0603-RES"))
    )
    (comp (ref "R11")
      (value "10k")
      (footprint "eagle-import:0603-RES")
      (libsource (lib "eagle-import") (part "RESISTOR0603-RES"))
    )
    (comp (ref "R12")
      (value "10k")
      (footprint "eagle-import:0603-RES")
      (libsource (lib "eagle-import") (part "RESISTOR0603-RES"))
    )
    (comp (ref "R13")
      (value "10k")
      (footprint "eagle-import:0603-RES")
      (libsource (lib "eagle-import") (part "RESISTOR0603-RES"))
    )
    (comp (ref "R14")
      (value "10k")
      (footprint "eagle-import:0603-RES")
      (libsource (lib "eagle-import") (part "RESISTOR0603-RES"))
    )
    (comp (ref "R15")
      (value "10k")
      (footprint "eagle-import:0603-RES")
      (libsource (lib "eagle-import") (part "RESISTOR0603-RES"))
    )
    (comp (ref "R16")
      (value "10k")
      (footprint "eagle-import:0603-RES")
      (libsource (lib "eagle-import") (part "RESISTOR0603-RES"))
    )
    (comp (ref "R17")
      (value "10k")
      (footprint "eagle-import:0603-RES")
      (libsource (lib "eagle-import") (part "RESISTOR0603-RES"))
    )
    (comp (ref "R18")
      (value "10k")
      (footprint "eagle-import:0603-RES")
      (libsource (lib "eagle-import") (part "RESISTOR0603-RES"))
    )
    (comp (ref "R19")
      (value "10k")
      (footprint "eagle-import:0603-RES")
      (libsource (lib "eagle-import") (part "RESISTOR0603-RES"))
    )
    (comp (ref "R20")
      (value "10k")
      (footprint "eagle-import:0603-RES")
      (libsource (lib "eagle-import") (part "RESISTOR0603-RES"))
    )
    (comp (ref "R21")
      (value "2K2")
      (footprint "eagle-import:0603-RES")
      (libsource (lib "eagle-import") (part "RESISTOR0603-RES"))
    )
    (comp (ref "R22")
      (value "2K2")
      (footprint "eagle-import:0603-RES")
      (libsource (lib "eagle-import") (part "RESISTOR0603-RES"))
    )
    (comp (ref "R23")
      (value "2K2")
      (footprint "eagle-import:0603-RES")
      (libsource (lib "eagle-import") (part "RESISTOR0603-RES"))
    )
    (comp (ref "R24")
      (value "2K2")
      (footprint "eagle-import:0603-RES")
      (libsource (lib "eagle-import") (part "RESISTOR0603-RES"))
    )
    (comp (ref "R25")
      (value "2K2")
      (footprint "eagle-import:0603-RES")
      (libsource (lib "eagle-import") (part "RESISTOR0603-RES"))
    )
    (comp (ref "R26")
      (value "2K2")
      (footprint "eagle-import:0603-RES")
      (libsource (lib "eagle-import") (part "RESISTOR0603-RES"))
    )
    (comp (ref "R27")
      (value "2K2")
      (footprint "eagle-import:0603-RES")
      (libsource (lib "eagle-import") (part "RESISTOR0603-RES"))
    )
    (comp (ref "R28")
      (value "2K2")
      (footprint "eagle-import:0603-RES")
      (libsource (lib "eagle-import") (part "RESISTOR0603-RES"))
    )
    (comp (ref "R29")
      (value "2K2")
      (footprint "eagle-import:0603-RES")
      (libsource (lib "eagle-import") (part "RESISTOR0603-RES"))
    )
    (comp (ref "R30")
      (value "DNF")
      (footprint "eagle-import:0603-RES")
      (libsource (lib "eagle-import") (part "RESISTOR0603-RES"))
    )
    (comp (ref "R31")
      (value "100k")
      (footprint "eagle-import:0603-RES")
      (libsource (lib "eagle-import") (part "RESISTOR0603-RES"))
    )
    (comp (ref "R32")
      (value "DNF")
      (footprint "eagle-import:0603-RES")
      (libsource (lib "eagle-import") (part "RESISTOR0603-RES"))
    )
    (comp (ref "R33")
      (value "100k")
      (footprint "eagle-import:0603-RES")
      (libsource (lib "eagle-import") (part "RESISTOR0603-RES"))
    )
    (comp (ref "R34")
      (value "DNF")
      (footprint "eagle-import:0603-RES")
      (libsource (lib "eagle-import") (part "RESISTOR0603-RES"))
    )
    (comp (ref "R35")
      (value "100k")
      (footprint "eagle-import:0603-RES")
      (libsource (lib "eagle-import") (part "RESISTOR0603-RES"))
    )
    (comp (ref "R36")
      (value "DNF")
      (footprint "eagle-import:0603-RES")
      (libsource (lib "eagle-import") (part "RESISTOR0603-RES"))
    )
    (comp (ref "R37")
      (value "100k")
      (footprint "eagle-import:0603-RES")
      (libsource (lib "eagle-import") (part "RESISTOR0603-RES"))
    )
    (comp (ref "R38")
      (value "DNF")
      (footprint "eagle-import:0603-RES")
      (libsource (lib "eagle-import") (part "RESISTOR0603-RES"))
    )
    (comp (ref "R39")
      (value "100k")
      (footprint "eagle-import:0603-RES")
      (libsource (lib "eagle-import") (part "RESISTOR0603-RES"))
    )
    (comp (ref "R40")
      (value "DNF")
      (footprint "eagle-import:0603-RES")
      (libsource (lib "eagle-import") (part "RESISTOR0603-RES"))
    )
    (comp (ref "R41")
      (value "100k")
      (footprint "eagle-import:0603-RES")
      (libsource (lib "eagle-import") (part "RESISTOR0603-RES"))
    )
    (comp (ref "R42")
      (value "DNF")
      (footprint "eagle-import:0603-RES")
      (libsource (lib "eagle-import") (part "RESISTOR0603-RES"))
    )
    (comp (ref "R43")
      (value "100k")
      (footprint "eagle-import:0603-RES")
      (libsource (lib "eagle-import") (part "RESISTOR0603-RES"))
    )
    (comp (ref "R44")
      (value "DNF")
      (footprint "eagle-import:0603-RES")
      (libsource (lib "eagle-import") (part "RESISTOR0603-RES"))
    )
    (comp (ref "R45")
      (value "100k")
      (footprint "eagle-import:0603-RES")
      (libsource (lib "eagle-import") (part "RESISTOR0603-RES"))
    )
    (comp (ref "R46")
      (value "DNF")
      (footprint "eagle-import:0603-RES")
      (libsource (lib "eagle-import") (part "RESISTOR0603-RES"))
    )
    (comp (ref "R47")
      (value "100k")
      (footprint "eagle-import:0603-RES")
      (libsource (lib "eagle-import") (part "RESISTOR0603-RES"))
    )
    (comp (ref "R48")
      (value "DNF")
      (footprint "eagle-import:0603-RES")
      (libsource (lib "eagle-import") (part "RESISTOR0603-RES"))
    )
    (comp (ref "R49")
      (value "100k")
      (footprint "eagle-import:0603-RES")
      (libsource (lib "eagle-import") (part "RESISTOR0603-RES"))
    )
    (comp (ref "R50")
      (value "DNF")
      (footprint "eagle-import:0603-RES")
      (libsource (lib "eagle-import") (part "RESISTOR0603-RES"))
    )
    (comp (ref "R51")
      (value "100k")
      (footprint "eagle-import:0603-RES")
      (libsource (lib "eagle-import") (part "RESISTOR0603-RES"))
    )
    (comp (ref "R52")
      (value "DNF")
      (footprint "eagle-import:0603-RES")
      (libsource (lib "eagle-import") (part "RESISTOR0603-RES"))
    )
    (comp (ref "R53")
      (value "100k")
      (footprint "eagle-import:0603-RES")
      (libsource (lib "eagle-import") (part "RESISTOR0603-RES"))
    )
    (comp (ref "R54")
      (value "DNF")
      (footprint "eagle-import:0603-RES")
      (libsource (lib "eagle-import") (part "RESISTOR0603-RES"))
    )
    (comp (ref "R55")
      (value "100k")
      (footprint "eagle-import:0603-RES")
      (libsource (lib "eagle-import") (part "RESISTOR0603-RES"))
    )
    (comp (ref "R56")
      (value "DNF")
      (footprint "eagle-import:0603-RES")
      (libsource (lib "eagle-import") (part "RESISTOR0603-RES"))
    )
    (comp (ref "R57")
      (value "100k")
      (footprint "eagle-import:0603-RES")
      (libsource (lib "eagle-import") (part "RESISTOR0603-RES"))
    )
    (comp (ref "R58")
      (value "DNF")
      (footprint "eagle-import:0603-RES")
      (libsource (lib "eagle-import") (part "RESISTOR0603-RES"))
    )
    (comp (ref "R59")
      (value "100k")
      (footprint "eagle-import:0603-RES")
      (libsource (lib "eagle-import") (part "RESISTOR0603-RES"))
    )
    (comp (ref "R60")
      (value "DNF")
      (footprint "eagle-import:0603-RES")
      (libsource (lib "eagle-import") (part "RESISTOR0603-RES"))
    )
    (comp (ref "R61")
      (value "100k")
      (footprint "eagle-import:0603-RES")
      (libsource (lib "eagle-import") (part "RESISTOR0603-RES"))
    )
    (comp (ref "R62")
      (value "DNF")
      (footprint "eagle-import:0603-RES")
      (libsource (lib "eagle-import") (part "RESISTOR0603-RES"))
    )
    (comp (ref "R63")
      (value "100k")
      (footprint "eagle-import:0603-RES")
      (libsource (lib "eagle-import") (part "RESISTOR0603-RES"))
    )
    (comp (ref "R64")
      (value "DNF")
      (footprint "eagle-import:0603-RES")
      (libsource (lib "eagle-import") (part "RESISTOR0603-RES"))
    )
    (comp (ref "R65")
      (value "100k")
      (footprint "eagle-import:0603-RES")
      (libsource (lib "eagle-import") (part "RESISTOR0603-RES"))
    )
    (comp (ref "R66")
      (value "DNF")
      (footprint "eagle-import:0603-RES")
      (libsource (lib "eagle-import") (part "RESISTOR0603-RES"))
    )
    (comp (ref "R67")
      (value "100k")
      (footprint "eagle-import:0603-RES")
      (libsource (lib "eagle-import") (part "RESISTOR0603-RES"))
    )
    (comp (ref "R68")
      (value "DNF")
      (footprint "eagle-import:0603-RES")
      (libsource (lib "eagle-import") (part "RESISTOR0603-RES"))
    )
    (comp (ref "R69")
      (value "100k")
      (footprint "eagle-import:0603-RES")
      (libsource (lib "eagle-import") (part "RESISTOR0603-RES"))
    )
    (comp (ref "R70")
      (value "DNF")
      (footprint "eagle-import:0603-RES")
      (libsource (lib "eagle-import") (part "RESISTOR0603-RES"))
    )
    (comp (ref "R71")
      (value "100k")
      (footprint "eagle-import:0603-RES")
      (libsource (lib "eagle-import") (part "RESISTOR0603-RES"))
    )
    (comp (ref "R72")
      (value "DNF")
      (footprint "eagle-import:0603-RES")
      (libsource (lib "eagle-import") (part "RESISTOR0603-RES"))
    )
    (comp (ref "R73")
      (value "100k")
      (footprint "eagle-import:0603-RES")
      (libsource (lib "eagle-import") (part "RESISTOR0603-RES"))
    )
    (comp (ref "R74")
      (value "DNF")
      (footprint "eagle-import:0603-RES")
      (libsource (lib "eagle-import") (part "RESISTOR0603-RES"))
    )
    (comp (ref "R75")
      (value "100k")
      (footprint "eagle-import:0603-RES")
      (libsource (lib "eagle-import") (part "RESISTOR0603-RES"))
    )
    (comp (ref "R76")
      (value "DNF")
      (footprint "eagle-import:0603-RES")
      (libsource (lib "eagle-import") (part "RESISTOR0603-RES"))
    )
    (comp (ref "R77")
      (value "100k")
      (footprint "eagle-import:0603-RES")
      (libsource (lib "eagle-import") (part "RESISTOR0603-RES"))
    )
    (comp (ref "R78")
      (value "DNF")
      (footprint "eagle-import:0603-RES")
      (libsource (lib "eagle-import") (part "RESISTOR0603-RES"))
    )
    (comp (ref "R79")
      (value "100k")
      (footprint "eagle-import:0603-RES")
      (libsource (lib "eagle-import") (part "RESISTOR0603-RES"))
    )
    (comp (ref "SJ1")
      (value "SOLDERJUMPERNO")
      (footprint "eagle-import:SJ_2S-NO")
      (libsource (lib "eagle-import") (part "SOLDERJUMPERNO"))
    )
    (comp (ref "SJ2")
      (value "SOLDERJUMPERNO")
      (footprint "eagle-import:SJ_2S-NO")
      (libsource (lib "eagle-import") (part "SOLDERJUMPERNO"))
    )
    (comp (ref "SJ3")
      (value "SOLDERJUMPERNO")
      (footprint "eagle-import:SJ_2S-NO")
      (libsource (lib "eagle-import") (part "SOLDERJUMPERNO"))
    )
    (comp (ref "SJ4")
      (value "SOLDERJUMPERNO")
      (footprint "eagle-import:SJ_2S-NO")
      (libsource (lib "eagle-import") (part "SOLDERJUMPERNO"))
    )
    (comp (ref "SJ5")
      (value "SOLDERJUMPERNO")
      (footprint "eagle-import:SJ_2S-NO")
      (libsource (lib "eagle-import") (part "SOLDERJUMPERNO"))
    )
    (comp (ref "SJ6")
      (value "SOLDERJUMPERNO")
      (footprint "eagle-import:SJ_2S-NO")
      (libsource (lib "eagle-import") (part "SOLDERJUMPERNO"))
    )
    (comp (ref "SJ7")
      (value "SOLDERJUMPERNO")
      (footprint "eagle-import:SJ_2S-NO")
      (libsource (lib "eagle-import") (part "SOLDERJUMPERNO"))
    )
    (comp (ref "SJ8")
      (value "SOLDERJUMPERNO")
      (footprint "eagle-import:SJ_2S-NO")
      (libsource (lib "eagle-import") (part "SOLDERJUMPERNO"))
    )
    (comp (ref "SJ9")
      (value "SOLDERJUMPERNO")
      (footprint "eagle-import:SJ_2S-NO")
      (libsource (lib "eagle-import") (part "SOLDERJUMPERNO"))
    )
    (comp (ref "SJ10")
      (value "SOLDERJUMPERNO")
      (footprint "eagle-import:SJ_2S-NO")
      (libsource (lib "eagle-import") (part "SOLDERJUMPERNO"))
    )
    (comp (ref "SJ11")
      (value "SOLDERJUMPERNO")
      (footprint "eagle-import:SJ_2S-NO")
      (libsource (lib "eagle-import") (part "SOLDERJUMPERNO"))
    )
    (comp (ref "SJ12")
      (value "SOLDERJUMPERNO")
      (footprint "eagle-import:SJ_2S-NO")
      (libsource (lib "eagle-import") (part "SOLDERJUMPERNO"))
    )
    (comp (ref "SJ13")
      (value "SOLDERJUMPERNO")
      (footprint "eagle-import:SJ_2S-NO")
      (libsource (lib "eagle-import") (part "SOLDERJUMPERNO"))
    )
    (comp (ref "STANDOFF1")
      (value "STAND-OFF")
      (footprint "eagle-import:STAND-OFF")
      (libsource (lib "eagle-import") (part "STAND-OFF"))
    )
    (comp (ref "STANDOFF2")
      (value "STAND-OFF")
      (footprint "eagle-import:STAND-OFF")
      (libsource (lib "eagle-import") (part "STAND-OFF"))
    )
    (comp (ref "STANDOFF3")
      (value "STAND-OFF")
      (footprint "eagle-import:STAND-OFF")
      (libsource (lib "eagle-import") (part "STAND-OFF"))
    )
    (comp (ref "STANDOFF4")
      (value "STAND-OFF")
      (footprint "eagle-import:STAND-OFF")
      (libsource (lib "eagle-import") (part "STAND-OFF"))
    )
    (comp (ref "STANDOFF5")
      (value "STAND-OFF")
      (footprint "eagle-import:STAND-OFF")
      (libsource (lib "eagle-import") (part "STAND-OFF"))
    )
    (comp (ref "STANDOFF6")
      (value "STAND-OFF")
      (footprint "eagle-import:STAND-OFF")
      (libsource (lib "eagle-import") (part "STAND-OFF"))
    )
    (comp (ref "STANDOFF7")
      (value "STAND-OFF")
      (footprint "eagle-import:STAND-OFF")
      (libsource (lib "eagle-import") (part "STAND-OFF"))
    )
    (comp (ref "TP1")
      (value "TEST-POINTTP_15TH_THRU")
      (footprint "eagle-import:TP_15TH")
      (libsource (lib "eagle-import") (part "TEST-POINTTP_15TH_THRU"))
    )
    (comp (ref "TP2")
      (value "TEST-POINTTP_15TH_THRU")
      (footprint "eagle-import:TP_15TH")
      (libsource (lib "eagle-import") (part "TEST-POINTTP_15TH_THRU"))
    )
  )
  (nets
    (net (code "1") (name "/5V_IN") (class "Default")
      (node (ref "C1") (pin "A") (pinfunction "+_A") (pintype "passive"))
      (node (ref "C2") (pin "1") (pinfunction "1_1") (pintype "passive"))
      (node (ref "CON1") (pin "P$1") (pinfunction "P$1_P$1") (pintype "bidirectional"))
      (node (ref "IC29") (pin "IN") (pinfunction "IN_IN") (pintype "input"))
      (node (ref "JP1") (pin "2") (pinfunction "2_2") (pintype "passive"))
    )
    (net (code "2") (name "/PGOOD_0") (class "Default")
      (node (ref "IC1") (pin "15") (pinfunction "DIN4_15") (pintype "input"))
      (node (ref "JP2") (pin "6") (pinfunction "6_6") (pintype "passive"))
      (node (ref "R11") (pin "1") (pinfunction "1_1") (pintype "passive"))
      (node (ref "SJ1") (pin "1") (pinfunction "1_1") (pintype "passive"))
    )
    (net (code "3") (name "/PGOOD_0_P") (class "Default")
      (node (ref "HDMI0") (pin "15") (pinfunction "15_15") (pintype "bidirectional"))
      (node (ref "IC1") (pin "14") (pinfunction "DOUT4+_14") (pintype "output"))
    )
    (net (code "4") (name "/PGOOD_1") (class "Default")
      (node (ref "IC3") (pin "15") (pinfunction "DIN4_15") (pintype "input"))
      (node (ref "JP2") (pin "5") (pinfunction "5_5") (pintype "passive"))
      (node (ref "R12") (pin "1") (pinfunction "1_1") (pintype "passive"))
      (node (ref "SJ2") (pin "1") (pinfunction "1_1") (pintype "passive"))
    )
    (net (code "5") (name "/PGOOD_2") (class "Default")
      (node (ref "IC5") (pin "15") (pinfunction "DIN4_15") (pintype "input"))
      (node (ref "JP2") (pin "4") (pinfunction "4_4") (pintype "passive"))
      (node (ref "R13") (pin "1") (pinfunction "1_1") (pintype "passive"))
      (node (ref "SJ3") (pin "2") (pinfunction "2_2") (pintype "passive"))
    )
    (net (code "6") (name "/PGOOD_3") (class "Default")
      (node (ref "IC7") (pin "15") (pinfunction "DIN4_15") (pintype "input"))
      (node (ref "JP2") (pin "3") (pinfunction "3_3") (pintype "passive"))
      (node (ref "R14") (pin "1") (pinfunction "1_1") (pintype "passive"))
      (node (ref "SJ4") (pin "2") (pinfunction "2_2") (pintype "passive"))
    )
    (net (code "7") (name "/PGOOD_4") (class "Default")
      (node (ref "IC9") (pin "15") (pinfunction "DIN4_15") (pintype "input"))
      (node (ref "JP2") (pin "2") (pinfunction "2_2") (pintype "passive"))
      (node (ref "R15") (pin "1") (pinfunction "1_1") (pintype "passive"))
      (node (ref "SJ5") (pin "2") (pinfunction "2_2") (pintype "passive"))
    )
    (net (code "8") (name "/PGOOD_5") (class "Default")
      (node (ref "IC11") (pin "15") (pinfunction "DIN4_15") (pintype "input"))
      (node (ref "JP11") (pin "6") (pinfunction "6_6") (pintype "passive"))
      (node (ref "R16") (pin "1") (pinfunction "1_1") (pintype "passive"))
      (node (ref "SJ6") (pin "1") (pinfunction "1_1") (pintype "passive"))
    )
    (net (code "9") (name "/PGOOD_6") (class "Default")
      (node (ref "IC13") (pin "15") (pinfunction "DIN4_15") (pintype "input"))
      (node (ref "JP11") (pin "5") (pinfunction "5_5") (pintype "passive"))
      (node (ref "R17") (pin "1") (pinfunction "1_1") (pintype "passive"))
      (node (ref "SJ7") (pin "1") (pinfunction "1_1") (pintype "passive"))
    )
    (net (code "10") (name "/PGOOD_7") (class "Default")
      (node (ref "IC15") (pin "15") (pinfunction "DIN4_15") (pintype "input"))
      (node (ref "JP11") (pin "4") (pinfunction "4_4") (pintype "passive"))
      (node (ref "R18") (pin "1") (pinfunction "1_1") (pintype "passive"))
      (node (ref "SJ8") (pin "1") (pinfunction "1_1") (pintype "passive"))
    )
    (net (code "11") (name "/PGOOD_8") (class "Default")
      (node (ref "IC17") (pin "15") (pinfunction "DIN4_15") (pintype "input"))
      (node (ref "JP11") (pin "3") (pinfunction "3_3") (pintype "passive"))
      (node (ref "R19") (pin "1") (pinfunction "1_1") (pintype "passive"))
      (node (ref "SJ9") (pin "1") (pinfunction "1_1") (pintype "passive"))
    )
    (net (code "12") (name "/PGOOD_9") (class "Default")
      (node (ref "IC19") (pin "15") (pinfunction "DIN4_15") (pintype "input"))
      (node (ref "JP11") (pin "2") (pinfunction "2_2") (pintype "passive"))
      (node (ref "R20") (pin "1") (pinfunction "1_1") (pintype "passive"))
      (node (ref "SJ10") (pin "1") (pinfunction "1_1") (pintype "passive"))
    )
    (net (code "13") (name "/PGOOG_0_N") (class "Default")
      (node (ref "HDMI0") (pin "16") (pinfunction "16_16") (pintype "bidirectional"))
      (node (ref "IC1") (pin "13") (pinfunction "DOUT4-_13") (pintype "output"))
    )
    (net (code "14") (name "/S0") (class "Default")
      (node (ref "IC21") (pin "11") (pinfunction "S0_11") (pintype "bidirectional"))
      (node (ref "IC22") (pin "11") (pinfunction "S0_11") (pintype "bidirectional"))
      (node (ref "IC23") (pin "11") (pinfunction "S0_11") (pintype "bidirectional"))
      (node (ref "IC24") (pin "11") (pinfunction "S0_11") (pintype "bidirectional"))
      (node (ref "IC25") (pin "11") (pinfunction "S0_11") (pintype "bidirectional"))
      (node (ref "IC26") (pin "11") (pinfunction "S0_11") (pintype "bidirectional"))
      (node (ref "IC27") (pin "11") (pinfunction "S0_11") (pintype "bidirectional"))
      (node (ref "IC28") (pin "11") (pinfunction "S0_11") (pintype "bidirectional"))
      (node (ref "JP1") (pin "6") (pinfunction "6_6") (pintype "passive"))
      (node (ref "R21") (pin "2") (pinfunction "2_2") (pintype "passive"))
    )
    (net (code "15") (name "/S1") (class "Default")
      (node (ref "IC21") (pin "10") (pinfunction "S1_10") (pintype "bidirectional"))
      (node (ref "IC22") (pin "10") (pinfunction "S1_10") (pintype "bidirectional"))
      (node (ref "IC23") (pin "10") (pinfunction "S1_10") (pintype "bidirectional"))
      (node (ref "IC24") (pin "10") (pinfunction "S1_10") (pintype "bidirectional"))
      (node (ref "IC25") (pin "10") (pinfunction "S1_10") (pintype "bidirectional"))
      (node (ref "IC26") (pin "10") (pinfunction "S1_10") (pintype "bidirectional"))
      (node (ref "IC27") (pin "10") (pinfunction "S1_10") (pintype "bidirectional"))
      (node (ref "IC28") (pin "10") (pinfunction "S1_10") (pintype "bidirectional"))
      (node (ref "JP1") (pin "5") (pinfunction "5_5") (pintype "passive"))
      (node (ref "R22") (pin "2") (pinfunction "2_2") (pintype "passive"))
    )
    (net (code "16") (name "/S2") (class "Default")
      (node (ref "IC21") (pin "9") (pinfunction "S2_9") (pintype "bidirectional"))
      (node (ref "IC22") (pin "9") (pinfunction "S2_9") (pintype "bidirectional"))
      (node (ref "IC23") (pin "9") (pinfunction "S2_9") (pintype "bidirectional"))
      (node (ref "IC24") (pin "9") (pinfunction "S2_9") (pintype "bidirectional"))
      (node (ref "IC25") (pin "9") (pinfunction "S2_9") (pintype "bidirectional"))
      (node (ref "IC26") (pin "9") (pinfunction "S2_9") (pintype "bidirectional"))
      (node (ref "IC27") (pin "9") (pinfunction "S2_9") (pintype "bidirectional"))
      (node (ref "IC28") (pin "9") (pinfunction "S2_9") (pintype "bidirectional"))
      (node (ref "JP1") (pin "4") (pinfunction "4_4") (pintype "passive"))
      (node (ref "R23") (pin "2") (pinfunction "2_2") (pintype "passive"))
    )
    (net (code "17") (name "/S3") (class "Default")
      (node (ref "IC21") (pin "6") (pinfunction "~{E}_6") (pintype "bidirectional"))
      (node (ref "IC23") (pin "6") (pinfunction "~{E}_6") (pintype "bidirectional"))
      (node (ref "IC25") (pin "6") (pinfunction "~{E}_6") (pintype "bidirectional"))
      (node (ref "IC27") (pin "6") (pinfunction "~{E}_6") (pintype "bidirectional"))
      (node (ref "IC30") (pin "2") (pinfunction "A_2") (pintype "input"))
      (node (ref "JP1") (pin "3") (pinfunction "3_3") (pintype "passive"))
      (node (ref "R24") (pin "2") (pinfunction "2_2") (pintype "passive"))
    )
    (net (code "18") (name "/TCK") (class "Default")
      (node (ref "IC21") (pin "3") (pinfunction "Z_3") (pintype "bidirectional"))
      (node (ref "IC22") (pin "3") (pinfunction "Z_3") (pintype "bidirectional"))
      (node (ref "MOD1") (pin "2") (pinfunction "TCK_2") (pintype "bidirectional"))
      (node (ref "R26") (pin "2") (pinfunction "2_2") (pintype "passive"))
    )
    (net (code "19") (name "/TCK_0") (class "Default")
      (node (ref "IC1") (pin "1") (pinfunction "DIN1_1") (pintype "input"))
      (node (ref "IC21") (pin "13") (pinfunction "Y0_13") (pintype "bidirectional"))
      (node (ref "R1") (pin "1") (pinfunction "1_1") (pintype "passive"))
      (node (ref "R2") (pin "2") (pinfunction "2_2") (pintype "passive"))
    )
    (net (code "20") (name "/TCK_0_NEG") (class "Default")
      (node (ref "HDMI0") (pin "6") (pinfunction "6_6") (pintype "bidirectional"))
      (node (ref "IC1") (pin "3") (pinfunction "DOUT1-_3") (pintype "output"))
    )
    (net (code "21") (name "/TCK_0_POS") (class "Default")
      (node (ref "HDMI0") (pin "4") (pinfunction "4_4") (pintype "bidirectional"))
      (node (ref "IC1") (pin "2") (pinfunction "DOUT1+_2") (pintype "output"))
    )
    (net (code "22") (name "/TCK_1") (class "Default")
      (node (ref "IC21") (pin "14") (pinfunction "Y1_14") (pintype "bidirectional"))
      (node (ref "IC3") (pin "1") (pinfunction "DIN1_1") (pintype "input"))
      (node (ref "R7") (pin "1") (pinfunction "1_1") (pintype "passive"))
      (node (ref "R8") (pin "2") (pinfunction "2_2") (pintype "passive"))
    )
    (net (code "23") (name "/TCK_2") (class "Default")
      (node (ref "IC21") (pin "15") (pinfunction "Y2_15") (pintype "bidirectional"))
      (node (ref "IC5") (pin "1") (pinfunction "DIN1_1") (pintype "input"))
      (node (ref "R32") (pin "1") (pinfunction "1_1") (pintype "passive"))
      (node (ref "R33") (pin "2") (pinfunction "2_2") (pintype "passive"))
    )
    (net (code "24") (name "/TCK_3") (class "Default")
      (node (ref "IC21") (pin "12") (pinfunction "Y3_12") (pintype "bidirectional"))
      (node (ref "IC7") (pin "1") (pinfunction "DIN1_1") (pintype "input"))
      (node (ref "R38") (pin "1") (pinfunction "1_1") (pintype "passive"))
      (node (ref "R39") (pin "2") (pinfunction "2_2") (pintype "passive"))
    )
    (net (code "25") (name "/TCK_4") (class "Default")
      (node (ref "IC21") (pin "1") (pinfunction "Y4_1") (pintype "bidirectional"))
      (node (ref "IC9") (pin "1") (pinfunction "DIN1_1") (pintype "input"))
      (node (ref "R44") (pin "1") (pinfunction "1_1") (pintype "passive"))
      (node (ref "R45") (pin "2") (pinfunction "2_2") (pintype "passive"))
    )
    (net (code "26") (name "/TCK_5") (class "Default")
      (node (ref "IC21") (pin "5") (pinfunction "Y5_5") (pintype "bidirectional"))
      (node (ref "JP3") (pin "6") (pinfunction "6_6") (pintype "passive"))
    )
    (net (code "27") (name "/TCK_5_2") (class "Default")
      (node (ref "IC11") (pin "1") (pinfunction "DIN1_1") (pintype "input"))
      (node (ref "JP4") (pin "6") (pinfunction "6_6") (pintype "passive"))
      (node (ref "R50") (pin "1") (pinfunction "1_1") (pintype "passive"))
      (node (ref "R51") (pin "2") (pinfunction "2_2") (pintype "passive"))
    )
    (net (code "28") (name "/TCK_6") (class "Default")
      (node (ref "IC21") (pin "2") (pinfunction "Y6_2") (pintype "bidirectional"))
      (node (ref "JP3") (pin "5") (pinfunction "5_5") (pintype "passive"))
    )
    (net (code "29") (name "/TCK_6_2") (class "Default")
      (node (ref "IC13") (pin "1") (pinfunction "DIN1_1") (pintype "input"))
      (node (ref "JP4") (pin "5") (pinfunction "5_5") (pintype "passive"))
      (node (ref "R56") (pin "1") (pinfunction "1_1") (pintype "passive"))
      (node (ref "R57") (pin "2") (pinfunction "2_2") (pintype "passive"))
    )
    (net (code "30") (name "/TCK_7") (class "Default")
      (node (ref "IC21") (pin "4") (pinfunction "Y7_4") (pintype "bidirectional"))
      (node (ref "JP3") (pin "4") (pinfunction "4_4") (pintype "passive"))
    )
    (net (code "31") (name "/TCK_7_2") (class "Default")
      (node (ref "IC15") (pin "1") (pinfunction "DIN1_1") (pintype "input"))
      (node (ref "JP4") (pin "4") (pinfunction "4_4") (pintype "passive"))
      (node (ref "R62") (pin "1") (pinfunction "1_1") (pintype "passive"))
      (node (ref "R63") (pin "2") (pinfunction "2_2") (pintype "passive"))
    )
    (net (code "32") (name "/TCK_8") (class "Default")
      (node (ref "IC22") (pin "13") (pinfunction "Y0_13") (pintype "bidirectional"))
      (node (ref "JP3") (pin "3") (pinfunction "3_3") (pintype "passive"))
    )
    (net (code "33") (name "/TCK_8_2") (class "Default")
      (node (ref "IC17") (pin "1") (pinfunction "DIN1_1") (pintype "input"))
      (node (ref "JP4") (pin "3") (pinfunction "3_3") (pintype "passive"))
      (node (ref "R68") (pin "1") (pinfunction "1_1") (pintype "passive"))
      (node (ref "R69") (pin "2") (pinfunction "2_2") (pintype "passive"))
    )
    (net (code "34") (name "/TCK_9") (class "Default")
      (node (ref "IC22") (pin "14") (pinfunction "Y1_14") (pintype "bidirectional"))
      (node (ref "JP3") (pin "2") (pinfunction "2_2") (pintype "passive"))
    )
    (net (code "35") (name "/TCK_9_2") (class "Default")
      (node (ref "IC19") (pin "1") (pinfunction "DIN1_1") (pintype "input"))
      (node (ref "JP4") (pin "2") (pinfunction "2_2") (pintype "passive"))
      (node (ref "R74") (pin "1") (pinfunction "1_1") (pintype "passive"))
      (node (ref "R75") (pin "2") (pinfunction "2_2") (pintype "passive"))
    )
    (net (code "36") (name "/TDI") (class "Default")
      (node (ref "IC23") (pin "3") (pinfunction "Z_3") (pintype "bidirectional"))
      (node (ref "IC24") (pin "3") (pinfunction "Z_3") (pintype "bidirectional"))
      (node (ref "MOD1") (pin "3") (pinfunction "TDI_3") (pintype "bidirectional"))
      (node (ref "R27") (pin "2") (pinfunction "2_2") (pintype "passive"))
    )
    (net (code "37") (name "/TDI_0") (class "Default")
      (node (ref "IC1") (pin "9") (pinfunction "DIN3_9") (pintype "input"))
      (node (ref "IC23") (pin "13") (pinfunction "Y0_13") (pintype "bidirectional"))
      (node (ref "R5") (pin "1") (pinfunction "1_1") (pintype "passive"))
      (node (ref "R6") (pin "2") (pinfunction "2_2") (pintype "passive"))
    )
    (net (code "38") (name "/TDI_0_N") (class "Default")
      (node (ref "HDMI0") (pin "12") (pinfunction "12_12") (pintype "bidirectional"))
      (node (ref "IC1") (pin "11") (pinfunction "DOUT3-_11") (pintype "output"))
    )
    (net (code "39") (name "/TDI_0_P") (class "Default")
      (node (ref "HDMI0") (pin "10") (pinfunction "10_10") (pintype "bidirectional"))
      (node (ref "IC1") (pin "10") (pinfunction "DOUT3+_10") (pintype "output"))
    )
    (net (code "40") (name "/TDI_1") (class "Default")
      (node (ref "IC23") (pin "14") (pinfunction "Y1_14") (pintype "bidirectional"))
      (node (ref "IC3") (pin "9") (pinfunction "DIN3_9") (pintype "input"))
      (node (ref "R30") (pin "1") (pinfunction "1_1") (pintype "passive"))
      (node (ref "R31") (pin "2") (pinfunction "2_2") (pintype "passive"))
    )
    (net (code "41") (name "/TDI_2") (class "Default")
      (node (ref "IC23") (pin "15") (pinfunction "Y2_15") (pintype "bidirectional"))
      (node (ref "IC5") (pin "9") (pinfunction "DIN3_9") (pintype "input"))
      (node (ref "R36") (pin "1") (pinfunction "1_1") (pintype "passive"))
      (node (ref "R37") (pin "2") (pinfunction "2_2") (pintype "passive"))
    )
    (net (code "42") (name "/TDI_3") (class "Default")
      (node (ref "IC23") (pin "12") (pinfunction "Y3_12") (pintype "bidirectional"))
      (node (ref "IC7") (pin "9") (pinfunction "DIN3_9") (pintype "input"))
      (node (ref "R42") (pin "1") (pinfunction "1_1") (pintype "passive"))
      (node (ref "R43") (pin "2") (pinfunction "2_2") (pintype "passive"))
    )
    (net (code "43") (name "/TDI_4") (class "Default")
      (node (ref "IC23") (pin "1") (pinfunction "Y4_1") (pintype "bidirectional"))
      (node (ref "IC9") (pin "9") (pinfunction "DIN3_9") (pintype "input"))
      (node (ref "R48") (pin "1") (pinfunction "1_1") (pintype "passive"))
      (node (ref "R49") (pin "2") (pinfunction "2_2") (pintype "passive"))
    )
    (net (code "44") (name "/TDI_5") (class "Default")
      (node (ref "IC23") (pin "5") (pinfunction "Y5_5") (pintype "bidirectional"))
      (node (ref "JP5") (pin "6") (pinfunction "6_6") (pintype "passive"))
    )
    (net (code "45") (name "/TDI_5_2") (class "Default")
      (node (ref "IC11") (pin "9") (pinfunction "DIN3_9") (pintype "input"))
      (node (ref "JP6") (pin "6") (pinfunction "6_6") (pintype "passive"))
      (node (ref "R54") (pin "1") (pinfunction "1_1") (pintype "passive"))
      (node (ref "R55") (pin "2") (pinfunction "2_2") (pintype "passive"))
    )
    (net (code "46") (name "/TDI_6") (class "Default")
      (node (ref "IC23") (pin "2") (pinfunction "Y6_2") (pintype "bidirectional"))
      (node (ref "JP5") (pin "5") (pinfunction "5_5") (pintype "passive"))
    )
    (net (code "47") (name "/TDI_6_2") (class "Default")
      (node (ref "IC13") (pin "9") (pinfunction "DIN3_9") (pintype "input"))
      (node (ref "JP6") (pin "5") (pinfunction "5_5") (pintype "passive"))
      (node (ref "R60") (pin "1") (pinfunction "1_1") (pintype "passive"))
      (node (ref "R61") (pin "2") (pinfunction "2_2") (pintype "passive"))
    )
    (net (code "48") (name "/TDI_7") (class "Default")
      (node (ref "IC23") (pin "4") (pinfunction "Y7_4") (pintype "bidirectional"))
      (node (ref "JP5") (pin "4") (pinfunction "4_4") (pintype "passive"))
    )
    (net (code "49") (name "/TDI_7_2") (class "Default")
      (node (ref "IC15") (pin "9") (pinfunction "DIN3_9") (pintype "input"))
      (node (ref "JP6") (pin "4") (pinfunction "4_4") (pintype "passive"))
      (node (ref "R66") (pin "1") (pinfunction "1_1") (pintype "passive"))
      (node (ref "R67") (pin "2") (pinfunction "2_2") (pintype "passive"))
    )
    (net (code "50") (name "/TDI_8") (class "Default")
      (node (ref "IC24") (pin "13") (pinfunction "Y0_13") (pintype "bidirectional"))
      (node (ref "JP5") (pin "3") (pinfunction "3_3") (pintype "passive"))
    )
    (net (code "51") (name "/TDI_8_2") (class "Default")
      (node (ref "IC17") (pin "9") (pinfunction "DIN3_9") (pintype "input"))
      (node (ref "JP6") (pin "3") (pinfunction "3_3") (pintype "passive"))
      (node (ref "R72") (pin "1") (pinfunction "1_1") (pintype "passive"))
      (node (ref "R73") (pin "2") (pinfunction "2_2") (pintype "passive"))
    )
    (net (code "52") (name "/TDI_9") (class "Default")
      (node (ref "IC24") (pin "14") (pinfunction "Y1_14") (pintype "bidirectional"))
      (node (ref "JP5") (pin "2") (pinfunction "2_2") (pintype "passive"))
    )
    (net (code "53") (name "/TDI_9_2") (class "Default")
      (node (ref "IC19") (pin "9") (pinfunction "DIN3_9") (pintype "input"))
      (node (ref "JP6") (pin "2") (pinfunction "2_2") (pintype "passive"))
      (node (ref "R78") (pin "1") (pinfunction "1_1") (pintype "passive"))
      (node (ref "R79") (pin "2") (pinfunction "2_2") (pintype "passive"))
    )
    (net (code "54") (name "/TDO") (class "Default")
      (node (ref "IC27") (pin "3") (pinfunction "Z_3") (pintype "bidirectional"))
      (node (ref "IC28") (pin "3") (pinfunction "Z_3") (pintype "bidirectional"))
      (node (ref "MOD1") (pin "8") (pinfunction "TDO_8") (pintype "bidirectional"))
      (node (ref "R29") (pin "2") (pinfunction "2_2") (pintype "passive"))
    )
    (net (code "55") (name "/TDO_0") (class "Default")
      (node (ref "IC2") (pin "5") (pinfunction "R_5") (pintype "output"))
      (node (ref "IC27") (pin "13") (pinfunction "Y0_13") (pintype "bidirectional"))
    )
    (net (code "56") (name "/TDO_0_N") (class "Default")
      (node (ref "HDMI0") (pin "3") (pinfunction "3_3") (pintype "bidirectional"))
      (node (ref "IC2") (pin "4") (pinfunction "B_4") (pintype "input"))
    )
    (net (code "57") (name "/TDO_0_P") (class "Default")
      (node (ref "HDMI0") (pin "1") (pinfunction "1_1") (pintype "bidirectional"))
      (node (ref "IC2") (pin "3") (pinfunction "A_3") (pintype "input"))
    )
    (net (code "58") (name "/TDO_1") (class "Default")
      (node (ref "IC27") (pin "14") (pinfunction "Y1_14") (pintype "bidirectional"))
      (node (ref "IC4") (pin "5") (pinfunction "R_5") (pintype "output"))
    )
    (net (code "59") (name "/TDO_1_N") (class "Default")
      (node (ref "HDMI1") (pin "3") (pinfunction "3_3") (pintype "bidirectional"))
      (node (ref "IC4") (pin "4") (pinfunction "B_4") (pintype "input"))
    )
    (net (code "60") (name "/TDO_1_P") (class "Default")
      (node (ref "HDMI1") (pin "1") (pinfunction "1_1") (pintype "bidirectional"))
      (node (ref "IC4") (pin "3") (pinfunction "A_3") (pintype "input"))
    )
    (net (code "61") (name "/TDO_2") (class "Default")
      (node (ref "IC27") (pin "15") (pinfunction "Y2_15") (pintype "bidirectional"))
      (node (ref "IC6") (pin "5") (pinfunction "R_5") (pintype "output"))
    )
    (net (code "62") (name "/TDO_2_N") (class "Default")
      (node (ref "HDMI2") (pin "3") (pinfunction "3_3") (pintype "bidirectional"))
      (node (ref "IC6") (pin "4") (pinfunction "B_4") (pintype "input"))
    )
    (net (code "63") (name "/TDO_2_P") (class "Default")
      (node (ref "HDMI2") (pin "1") (pinfunction "1_1") (pintype "bidirectional"))
      (node (ref "IC6") (pin "3") (pinfunction "A_3") (pintype "input"))
    )
    (net (code "64") (name "/TDO_3") (class "Default")
      (node (ref "IC27") (pin "12") (pinfunction "Y3_12") (pintype "bidirectional"))
      (node (ref "IC8") (pin "5") (pinfunction "R_5") (pintype "output"))
    )
    (net (code "65") (name "/TDO_3_N") (class "Default")
      (node (ref "HDMI3") (pin "3") (pinfunction "3_3") (pintype "bidirectional"))
      (node (ref "IC8") (pin "4") (pinfunction "B_4") (pintype "input"))
    )
    (net (code "66") (name "/TDO_3_P") (class "Default")
      (node (ref "HDMI3") (pin "1") (pinfunction "1_1") (pintype "bidirectional"))
      (node (ref "IC8") (pin "3") (pinfunction "A_3") (pintype "input"))
    )
    (net (code "67") (name "/TDO_4") (class "Default")
      (node (ref "IC10") (pin "5") (pinfunction "R_5") (pintype "output"))
      (node (ref "IC27") (pin "1") (pinfunction "Y4_1") (pintype "bidirectional"))
    )
    (net (code "68") (name "/TDO_4_N") (class "Default")
      (node (ref "HDMI4") (pin "3") (pinfunction "3_3") (pintype "bidirectional"))
      (node (ref "IC10") (pin "4") (pinfunction "B_4") (pintype "input"))
    )
    (net (code "69") (name "/TDO_4_P") (class "Default")
      (node (ref "HDMI4") (pin "1") (pinfunction "1_1") (pintype "bidirectional"))
      (node (ref "IC10") (pin "3") (pinfunction "A_3") (pintype "input"))
    )
    (net (code "70") (name "/TDO_5") (class "Default")
      (node (ref "IC27") (pin "5") (pinfunction "Y5_5") (pintype "bidirectional"))
      (node (ref "JP9") (pin "6") (pinfunction "6_6") (pintype "passive"))
    )
    (net (code "71") (name "/TDO_5_2") (class "Default")
      (node (ref "IC12") (pin "5") (pinfunction "R_5") (pintype "output"))
      (node (ref "JP10") (pin "6") (pinfunction "6_6") (pintype "passive"))
    )
    (net (code "72") (name "/TDO_5_N") (class "Default")
      (node (ref "HDMI5") (pin "3") (pinfunction "3_3") (pintype "bidirectional"))
      (node (ref "IC12") (pin "4") (pinfunction "B_4") (pintype "input"))
    )
    (net (code "73") (name "/TDO_5_P") (class "Default")
      (node (ref "HDMI5") (pin "1") (pinfunction "1_1") (pintype "bidirectional"))
      (node (ref "IC12") (pin "3") (pinfunction "A_3") (pintype "input"))
    )
    (net (code "74") (name "/TDO_6") (class "Default")
      (node (ref "IC27") (pin "2") (pinfunction "Y6_2") (pintype "bidirectional"))
      (node (ref "JP9") (pin "5") (pinfunction "5_5") (pintype "passive"))
    )
    (net (code "75") (name "/TDO_6_2") (class "Default")
      (node (ref "IC14") (pin "5") (pinfunction "R_5") (pintype "output"))
      (node (ref "JP10") (pin "5") (pinfunction "5_5") (pintype "passive"))
    )
    (net (code "76") (name "/TDO_6_N") (class "Default")
      (node (ref "HDMI6") (pin "3") (pinfunction "3_3") (pintype "bidirectional"))
      (node (ref "IC14") (pin "4") (pinfunction "B_4") (pintype "input"))
    )
    (net (code "77") (name "/TDO_6_P") (class "Default")
      (node (ref "HDMI6") (pin "1") (pinfunction "1_1") (pintype "bidirectional"))
      (node (ref "IC14") (pin "3") (pinfunction "A_3") (pintype "input"))
    )
    (net (code "78") (name "/TDO_7") (class "Default")
      (node (ref "IC27") (pin "4") (pinfunction "Y7_4") (pintype "bidirectional"))
      (node (ref "JP9") (pin "4") (pinfunction "4_4") (pintype "passive"))
    )
    (net (code "79") (name "/TDO_7_2") (class "Default")
      (node (ref "IC16") (pin "5") (pinfunction "R_5") (pintype "output"))
      (node (ref "JP10") (pin "4") (pinfunction "4_4") (pintype "passive"))
    )
    (net (code "80") (name "/TDO_7_N") (class "Default")
      (node (ref "HDMI7") (pin "3") (pinfunction "3_3") (pintype "bidirectional"))
      (node (ref "IC16") (pin "4") (pinfunction "B_4") (pintype "input"))
    )
    (net (code "81") (name "/TDO_7_P") (class "Default")
      (node (ref "HDMI7") (pin "1") (pinfunction "1_1") (pintype "bidirectional"))
      (node (ref "IC16") (pin "3") (pinfunction "A_3") (pintype "input"))
    )
    (net (code "82") (name "/TDO_8") (class "Default")
      (node (ref "IC28") (pin "13") (pinfunction "Y0_13") (pintype "bidirectional"))
      (node (ref "JP9") (pin "3") (pinfunction "3_3") (pintype "passive"))
    )
    (net (code "83") (name "/TDO_8_2") (class "Default")
      (node (ref "IC18") (pin "5") (pinfunction "R_5") (pintype "output"))
      (node (ref "JP10") (pin "3") (pinfunction "3_3") (pintype "passive"))
    )
    (net (code "84") (name "/TDO_8_N") (class "Default")
      (node (ref "HDMI8") (pin "3") (pinfunction "3_3") (pintype "bidirectional"))
      (node (ref "IC18") (pin "4") (pinfunction "B_4") (pintype "input"))
    )
    (net (code "85") (name "/TDO_8_P") (class "Default")
      (node (ref "HDMI8") (pin "1") (pinfunction "1_1") (pintype "bidirectional"))
      (node (ref "IC18") (pin "3") (pinfunction "A_3") (pintype "input"))
    )
    (net (code "86") (name "/TDO_9") (class "Default")
      (node (ref "IC28") (pin "14") (pinfunction "Y1_14") (pintype "bidirectional"))
      (node (ref "JP9") (pin "2") (pinfunction "2_2") (pintype "passive"))
    )
    (net (code "87") (name "/TDO_9_2") (class "Default")
      (node (ref "IC20") (pin "5") (pinfunction "R_5") (pintype "output"))
      (node (ref "JP10") (pin "2") (pinfunction "2_2") (pintype "passive"))
    )
    (net (code "88") (name "/TDO_9_N") (class "Default")
      (node (ref "HDMI9") (pin "3") (pinfunction "3_3") (pintype "bidirectional"))
      (node (ref "IC20") (pin "4") (pinfunction "B_4") (pintype "input"))
    )
    (net (code "89") (name "/TDO_9_P") (class "Default")
      (node (ref "HDMI9") (pin "1") (pinfunction "1_1") (pintype "bidirectional"))
      (node (ref "IC20") (pin "3") (pinfunction "A_3") (pintype "input"))
    )
    (net (code "90") (name "/TMS") (class "Default")
      (node (ref "IC25") (pin "3") (pinfunction "Z_3") (pintype "bidirectional"))
      (node (ref "IC26") (pin "3") (pinfunction "Z_3") (pintype "bidirectional"))
      (node (ref "MOD1") (pin "4") (pinfunction "TMS_4") (pintype "bidirectional"))
      (node (ref "R28") (pin "2") (pinfunction "2_2") (pintype "passive"))
    )
    (net (code "91") (name "/TMS_0") (class "Default")
      (node (ref "IC1") (pin "7") (pinfunction "DIN2_7") (pintype "input"))
      (node (ref "IC25") (pin "13") (pinfunction "Y0_13") (pintype "bidirectional"))
      (node (ref "R3") (pin "1") (pinfunction "1_1") (pintype "passive"))
      (node (ref "R4") (pin "2") (pinfunction "2_2") (pintype "passive"))
    )
    (net (code "92") (name "/TMS_0_N") (class "Default")
      (node (ref "HDMI0") (pin "9") (pinfunction "9_9") (pintype "bidirectional"))
      (node (ref "IC1") (pin "5") (pinfunction "DOUT2-_5") (pintype "output"))
    )
    (net (code "93") (name "/TMS_0_P") (class "Default")
      (node (ref "HDMI0") (pin "7") (pinfunction "7_7") (pintype "bidirectional"))
      (node (ref "IC1") (pin "6") (pinfunction "DOUT2+_6") (pintype "output"))
    )
    (net (code "94") (name "/TMS_1") (class "Default")
      (node (ref "IC25") (pin "14") (pinfunction "Y1_14") (pintype "bidirectional"))
      (node (ref "IC3") (pin "7") (pinfunction "DIN2_7") (pintype "input"))
      (node (ref "R10") (pin "2") (pinfunction "2_2") (pintype "passive"))
      (node (ref "R9") (pin "1") (pinfunction "1_1") (pintype "passive"))
    )
    (net (code "95") (name "/TMS_2") (class "Default")
      (node (ref "IC25") (pin "15") (pinfunction "Y2_15") (pintype "bidirectional"))
      (node (ref "IC5") (pin "7") (pinfunction "DIN2_7") (pintype "input"))
      (node (ref "R34") (pin "1") (pinfunction "1_1") (pintype "passive"))
      (node (ref "R35") (pin "2") (pinfunction "2_2") (pintype "passive"))
    )
    (net (code "96") (name "/TMS_3") (class "Default")
      (node (ref "IC25") (pin "12") (pinfunction "Y3_12") (pintype "bidirectional"))
      (node (ref "IC7") (pin "7") (pinfunction "DIN2_7") (pintype "input"))
      (node (ref "R40") (pin "1") (pinfunction "1_1") (pintype "passive"))
      (node (ref "R41") (pin "2") (pinfunction "2_2") (pintype "passive"))
    )
    (net (code "97") (name "/TMS_4") (class "Default")
      (node (ref "IC25") (pin "1") (pinfunction "Y4_1") (pintype "bidirectional"))
      (node (ref "IC9") (pin "7") (pinfunction "DIN2_7") (pintype "input"))
      (node (ref "R46") (pin "1") (pinfunction "1_1") (pintype "passive"))
      (node (ref "R47") (pin "2") (pinfunction "2_2") (pintype "passive"))
    )
    (net (code "98") (name "/TMS_5") (class "Default")
      (node (ref "IC25") (pin "5") (pinfunction "Y5_5") (pintype "bidirectional"))
      (node (ref "JP7") (pin "6") (pinfunction "6_6") (pintype "passive"))
    )
    (net (code "99") (name "/TMS_5_2") (class "Default")
      (node (ref "IC11") (pin "7") (pinfunction "DIN2_7") (pintype "input"))
      (node (ref "JP8") (pin "6") (pinfunction "6_6") (pintype "passive"))
      (node (ref "R52") (pin "1") (pinfunction "1_1") (pintype "passive"))
      (node (ref "R53") (pin "2") (pinfunction "2_2") (pintype "passive"))
    )
    (net (code "100") (name "/TMS_6") (class "Default")
      (node (ref "IC25") (pin "2") (pinfunction "Y6_2") (pintype "bidirectional"))
      (node (ref "JP7") (pin "5") (pinfunction "5_5") (pintype "passive"))
    )
    (net (code "101") (name "/TMS_6_2") (class "Default")
      (node (ref "IC13") (pin "7") (pinfunction "DIN2_7") (pintype "input"))
      (node (ref "JP8") (pin "5") (pinfunction "5_5") (pintype "passive"))
      (node (ref "R58") (pin "1") (pinfunction "1_1") (pintype "passive"))
      (node (ref "R59") (pin "2") (pinfunction "2_2") (pintype "passive"))
    )
    (net (code "102") (name "/TMS_7") (class "Default")
      (node (ref "IC25") (pin "4") (pinfunction "Y7_4") (pintype "bidirectional"))
      (node (ref "JP7") (pin "4") (pinfunction "4_4") (pintype "passive"))
    )
    (net (code "103") (name "/TMS_7_2") (class "Default")
      (node (ref "IC15") (pin "7") (pinfunction "DIN2_7") (pintype "input"))
      (node (ref "JP8") (pin "4") (pinfunction "4_4") (pintype "passive"))
      (node (ref "R64") (pin "1") (pinfunction "1_1") (pintype "passive"))
      (node (ref "R65") (pin "2") (pinfunction "2_2") (pintype "passive"))
    )
    (net (code "104") (name "/TMS_8") (class "Default")
      (node (ref "IC26") (pin "13") (pinfunction "Y0_13") (pintype "bidirectional"))
      (node (ref "JP7") (pin "3") (pinfunction "3_3") (pintype "passive"))
    )
    (net (code "105") (name "/TMS_8_2") (class "Default")
      (node (ref "IC17") (pin "7") (pinfunction "DIN2_7") (pintype "input"))
      (node (ref "JP8") (pin "3") (pinfunction "3_3") (pintype "passive"))
      (node (ref "R70") (pin "1") (pinfunction "1_1") (pintype "passive"))
      (node (ref "R71") (pin "2") (pinfunction "2_2") (pintype "passive"))
    )
    (net (code "106") (name "/TMS_9") (class "Default")
      (node (ref "IC26") (pin "14") (pinfunction "Y1_14") (pintype "bidirectional"))
      (node (ref "JP7") (pin "2") (pinfunction "2_2") (pintype "passive"))
    )
    (net (code "107") (name "/TMS_9_2") (class "Default")
      (node (ref "IC19") (pin "7") (pinfunction "DIN2_7") (pintype "input"))
      (node (ref "JP8") (pin "2") (pinfunction "2_2") (pintype "passive"))
      (node (ref "R76") (pin "1") (pinfunction "1_1") (pintype "passive"))
      (node (ref "R77") (pin "2") (pinfunction "2_2") (pintype "passive"))
    )
    (net (code "108") (name "/~{S3}") (class "Default")
      (node (ref "IC22") (pin "6") (pinfunction "~{E}_6") (pintype "bidirectional"))
      (node (ref "IC24") (pin "6") (pinfunction "~{E}_6") (pintype "bidirectional"))
      (node (ref "IC26") (pin "6") (pinfunction "~{E}_6") (pintype "bidirectional"))
      (node (ref "IC28") (pin "6") (pinfunction "~{E}_6") (pintype "bidirectional"))
      (node (ref "IC30") (pin "4") (pinfunction "Y_4") (pintype "output"))
    )
    (net (code "109") (name "3.3V") (class "Default")
      (node (ref "C10") (pin "1") (pinfunction "1_1") (pintype "passive"))
      (node (ref "C11") (pin "1") (pinfunction "1_1") (pintype "passive"))
      (node (ref "C12") (pin "1") (pinfunction "1_1") (pintype "passive"))
      (node (ref "C13") (pin "1") (pinfunction "1_1") (pintype "passive"))
      (node (ref "C14") (pin "2") (pinfunction "2_2") (pintype "passive"))
      (node (ref "C15") (pin "2") (pinfunction "2_2") (pintype "passive"))
      (node (ref "C16") (pin "2") (pinfunction "2_2") (pintype "passive"))
      (node (ref "C17") (pin "2") (pinfunction "2_2") (pintype "passive"))
      (node (ref "C18") (pin "2") (pinfunction "2_2") (pintype "passive"))
      (node (ref "C19") (pin "2") (pinfunction "2_2") (pintype "passive"))
      (node (ref "C20") (pin "2") (pinfunction "2_2") (pintype "passive"))
      (node (ref "C21") (pin "2") (pinfunction "2_2") (pintype "passive"))
      (node (ref "C22") (pin "2") (pinfunction "2_2") (pintype "passive"))
      (node (ref "C23") (pin "2") (pinfunction "2_2") (pintype "passive"))
      (node (ref "C24") (pin "2") (pinfunction "2_2") (pintype "passive"))
      (node (ref "C25") (pin "2") (pinfunction "2_2") (pintype "passive"))
      (node (ref "C26") (pin "2") (pinfunction "2_2") (pintype "passive"))
      (node (ref "C27") (pin "2") (pinfunction "2_2") (pintype "passive"))
      (node (ref "C28") (pin "2") (pinfunction "2_2") (pintype "passive"))
      (node (ref "C29") (pin "2") (pinfunction "2_2") (pintype "passive"))
      (node (ref "C3") (pin "1") (pinfunction "1_1") (pintype "passive"))
      (node (ref "C30") (pin "2") (pinfunction "2_2") (pintype "passive"))
      (node (ref "C31") (pin "2") (pinfunction "2_2") (pintype "passive"))
      (node (ref "C32") (pin "2") (pinfunction "2_2") (pintype "passive"))
      (node (ref "C33") (pin "2") (pinfunction "2_2") (pintype "passive"))
      (node (ref "C34") (pin "2") (pinfunction "2_2") (pintype "passive"))
      (node (ref "C35") (pin "1") (pinfunction "1_1") (pintype "passive"))
      (node (ref "C36") (pin "A") (pinfunction "+_A") (pintype "passive"))
      (node (ref "C37") (pin "1") (pinfunction "1_1") (pintype "passive"))
      (node (ref "C4") (pin "A") (pinfunction "+_A") (pintype "passive"))
      (node (ref "C5") (pin "1") (pinfunction "1_1") (pintype "passive"))
      (node (ref "C6") (pin "1") (pinfunction "1_1") (pintype "passive"))
      (node (ref "C7") (pin "1") (pinfunction "1_1") (pintype "passive"))
      (node (ref "C8") (pin "1") (pinfunction "1_1") (pintype "passive"))
      (node (ref "C9") (pin "1") (pinfunction "1_1") (pintype "passive"))
      (node (ref "D9") (pin "A") (pinfunction "A_A") (pintype "passive"))
      (node (ref "IC1") (pin "16") (pinfunction "VCC_16") (pintype "power_in"))
      (node (ref "IC1") (pin "4") (pinfunction "EN_4") (pintype "input"))
      (node (ref "IC10") (pin "1") (pinfunction "VCC_1") (pintype "power_in"))
      (node (ref "IC11") (pin "16") (pinfunction "VCC_16") (pintype "power_in"))
      (node (ref "IC11") (pin "4") (pinfunction "EN_4") (pintype "input"))
      (node (ref "IC12") (pin "1") (pinfunction "VCC_1") (pintype "power_in"))
      (node (ref "IC13") (pin "16") (pinfunction "VCC_16") (pintype "power_in"))
      (node (ref "IC13") (pin "4") (pinfunction "EN_4") (pintype "input"))
      (node (ref "IC14") (pin "1") (pinfunction "VCC_1") (pintype "power_in"))
      (node (ref "IC15") (pin "16") (pinfunction "VCC_16") (pintype "power_in"))
      (node (ref "IC15") (pin "4") (pinfunction "EN_4") (pintype "input"))
      (node (ref "IC16") (pin "1") (pinfunction "VCC_1") (pintype "power_in"))
      (node (ref "IC17") (pin "16") (pinfunction "VCC_16") (pintype "power_in"))
      (node (ref "IC17") (pin "4") (pinfunction "EN_4") (pintype "input"))
      (node (ref "IC18") (pin "1") (pinfunction "VCC_1") (pintype "power_in"))
      (node (ref "IC19") (pin "16") (pinfunction "VCC_16") (pintype "power_in"))
      (node (ref "IC19") (pin "4") (pinfunction "EN_4") (pintype "input"))
      (node (ref "IC2") (pin "1") (pinfunction "VCC_1") (pintype "power_in"))
      (node (ref "IC20") (pin "1") (pinfunction "VCC_1") (pintype "power_in"))
      (node (ref "IC21") (pin "16") (pinfunction "VCC_16") (pintype "bidirectional"))
      (node (ref "IC22") (pin "16") (pinfunction "VCC_16") (pintype "bidirectional"))
      (node (ref "IC23") (pin "16") (pinfunction "VCC_16") (pintype "bidirectional"))
      (node (ref "IC24") (pin "16") (pinfunction "VCC_16") (pintype "bidirectional"))
      (node (ref "IC25") (pin "16") (pinfunction "VCC_16") (pintype "bidirectional"))
      (node (ref "IC26") (pin "16") (pinfunction "VCC_16") (pintype "bidirectional"))
      (node (ref "IC27") (pin "16") (pinfunction "VCC_16") (pintype "bidirectional"))
      (node (ref "IC28") (pin "16") (pinfunction "VCC_16") (pintype "bidirectional"))
      (node (ref "IC29") (pin "OUT") (pinfunction "OUT_OUT") (pintype "output"))
      (node (ref "IC3") (pin "16") (pinfunction "VCC_16") (pintype "power_in"))
      (node (ref "IC3") (pin "4") (pinfunction "EN_4") (pintype "input"))
      (node (ref "IC30") (pin "5") (pinfunction "VCC_5") (pintype "power_in"))
      (node (ref "IC4") (pin "1") (pinfunction "VCC_1") (pintype "power_in"))
      (node (ref "IC5") (pin "16") (pinfunction "VCC_16") (pintype "power_in"))
      (node (ref "IC5") (pin "4") (pinfunction "EN_4") (pintype "input"))
      (node (ref "IC6") (pin "1") (pinfunction "VCC_1") (pintype "power_in"))
      (node (ref "IC7") (pin "16") (pinfunction "VCC_16") (pintype "power_in"))
      (node (ref "IC7") (pin "4") (pinfunction "EN_4") (pintype "input"))
      (node (ref "IC8") (pin "1") (pinfunction "VCC_1") (pintype "power_in"))
      (node (ref "IC9") (pin "16") (pinfunction "VCC_16") (pintype "power_in"))
      (node (ref "IC9") (pin "4") (pinfunction "EN_4") (pintype "input"))
      (node (ref "JP12") (pin "2") (pinfunction "2_2") (pintype "passive"))
      (node (ref "JP13") (pin "2") (pinfunction "2_2") (pintype "passive"))
      (node (ref "MOD1") (pin "11") (pinfunction "VDD_11") (pintype "bidirectional"))
      (node (ref "MOD1") (pin "9") (pinfunction "VREF_9") (pintype "bidirectional"))
      (node (ref "R1") (pin "2") (pinfunction "2_2") (pintype "passive"))
      (node (ref "R11") (pin "2") (pinfunction "2_2") (pintype "passive"))
      (node (ref "R12") (pin "2") (pinfunction "2_2") (pintype "passive"))
      (node (ref "R13") (pin "2") (pinfunction "2_2") (pintype "passive"))
      (node (ref "R14") (pin "2") (pinfunction "2_2") (pintype "passive"))
      (node (ref "R15") (pin "2") (pinfunction "2_2") (pintype "passive"))
      (node (ref "R16") (pin "2") (pinfunction "2_2") (pintype "passive"))
      (node (ref "R17") (pin "2") (pinfunction "2_2") (pintype "passive"))
      (node (ref "R18") (pin "2") (pinfunction "2_2") (pintype "passive"))
      (node (ref "R19") (pin "2") (pinfunction "2_2") (pintype "passive"))
      (node (ref "R20") (pin "2") (pinfunction "2_2") (pintype "passive"))
      (node (ref "R3") (pin "2") (pinfunction "2_2") (pintype "passive"))
      (node (ref "R30") (pin "2") (pinfunction "2_2") (pintype "passive"))
      (node (ref "R32") (pin "2") (pinfunction "2_2") (pintype "passive"))
      (node (ref "R34") (pin "2") (pinfunction "2_2") (pintype "passive"))
      (node (ref "R36") (pin "2") (pinfunction "2_2") (pintype "passive"))
      (node (ref "R38") (pin "2") (pinfunction "2_2") (pintype "passive"))
      (node (ref "R40") (pin "2") (pinfunction "2_2") (pintype "passive"))
      (node (ref "R42") (pin "2") (pinfunction "2_2") (pintype "passive"))
      (node (ref "R44") (pin "2") (pinfunction "2_2") (pintype "passive"))
      (node (ref "R46") (pin "2") (pinfunction "2_2") (pintype "passive"))
      (node (ref "R48") (pin "2") (pinfunction "2_2") (pintype "passive"))
      (node (ref "R5") (pin "2") (pinfunction "2_2") (pintype "passive"))
      (node (ref "R50") (pin "2") (pinfunction "2_2") (pintype "passive"))
      (node (ref "R52") (pin "2") (pinfunction "2_2") (pintype "passive"))
      (node (ref "R54") (pin "2") (pinfunction "2_2") (pintype "passive"))
      (node (ref "R56") (pin "2") (pinfunction "2_2") (pintype "passive"))
      (node (ref "R58") (pin "2") (pinfunction "2_2") (pintype "passive"))
      (node (ref "R60") (pin "2") (pinfunction "2_2") (pintype "passive"))
      (node (ref "R62") (pin "2") (pinfunction "2_2") (pintype "passive"))
      (node (ref "R64") (pin "2") (pinfunction "2_2") (pintype "passive"))
      (node (ref "R66") (pin "2") (pinfunction "2_2") (pintype "passive"))
      (node (ref "R68") (pin "2") (pinfunction "2_2") (pintype "passive"))
      (node (ref "R7") (pin "2") (pinfunction "2_2") (pintype "passive"))
      (node (ref "R70") (pin "2") (pinfunction "2_2") (pintype "passive"))
      (node (ref "R72") (pin "2") (pinfunction "2_2") (pintype "passive"))
      (node (ref "R74") (pin "2") (pinfunction "2_2") (pintype "passive"))
      (node (ref "R76") (pin "2") (pinfunction "2_2") (pintype "passive"))
      (node (ref "R78") (pin "2") (pinfunction "2_2") (pintype "passive"))
      (node (ref "R9") (pin "2") (pinfunction "2_2") (pintype "passive"))
      (node (ref "TP1") (pin "P$1") (pinfunction "1_P$1") (pintype "bidirectional"))
    )
    (net (code "110") (name "GND") (class "Default")
      (node (ref "C1") (pin "C") (pinfunction "-_C") (pintype "passive"))
      (node (ref "C10") (pin "2") (pinfunction "2_2") (pintype "passive"))
      (node (ref "C11") (pin "2") (pinfunction "2_2") (pintype "passive"))
      (node (ref "C12") (pin "2") (pinfunction "2_2") (pintype "passive"))
      (node (ref "C13") (pin "2") (pinfunction "2_2") (pintype "passive"))
      (node (ref "C14") (pin "1") (pinfunction "1_1") (pintype "passive"))
      (node (ref "C15") (pin "1") (pinfunction "1_1") (pintype "passive"))
      (node (ref "C16") (pin "1") (pinfunction "1_1") (pintype "passive"))
      (node (ref "C17") (pin "1") (pinfunction "1_1") (pintype "passive"))
      (node (ref "C18") (pin "1") (pinfunction "1_1") (pintype "passive"))
      (node (ref "C19") (pin "1") (pinfunction "1_1") (pintype "passive"))
      (node (ref "C2") (pin "2") (pinfunction "2_2") (pintype "passive"))
      (node (ref "C20") (pin "1") (pinfunction "1_1") (pintype "passive"))
      (node (ref "C21") (pin "1") (pinfunction "1_1") (pintype "passive"))
      (node (ref "C22") (pin "1") (pinfunction "1_1") (pintype "passive"))
      (node (ref "C23") (pin "1") (pinfunction "1_1") (pintype "passive"))
      (node (ref "C24") (pin "1") (pinfunction "1_1") (pintype "passive"))
      (node (ref "C25") (pin "1") (pinfunction "1_1") (pintype "passive"))
      (node (ref "C26") (pin "1") (pinfunction "1_1") (pintype "passive"))
      (node (ref "C27") (pin "1") (pinfunction "1_1") (pintype "passive"))
      (node (ref "C28") (pin "1") (pinfunction "1_1") (pintype "passive"))
      (node (ref "C29") (pin "1") (pinfunction "1_1") (pintype "passive"))
      (node (ref "C3") (pin "2") (pinfunction "2_2") (pintype "passive"))
      (node (ref "C30") (pin "1") (pinfunction "1_1") (pintype "passive"))
      (node (ref "C31") (pin "1") (pinfunction "1_1") (pintype "passive"))
      (node (ref "C32") (pin "1") (pinfunction "1_1") (pintype "passive"))
      (node (ref "C33") (pin "1") (pinfunction "1_1") (pintype "passive"))
      (node (ref "C34") (pin "1") (pinfunction "1_1") (pintype "passive"))
      (node (ref "C35") (pin "2") (pinfunction "2_2") (pintype "passive"))
      (node (ref "C36") (pin "C") (pinfunction "-_C") (pintype "passive"))
      (node (ref "C37") (pin "2") (pinfunction "2_2") (pintype "passive"))
      (node (ref "C4") (pin "C") (pinfunction "-_C") (pintype "passive"))
      (node (ref "C5") (pin "2") (pinfunction "2_2") (pintype "passive"))
      (node (ref "C6") (pin "2") (pinfunction "2_2") (pintype "passive"))
      (node (ref "C7") (pin "2") (pinfunction "2_2") (pintype "passive"))
      (node (ref "C8") (pin "2") (pinfunction "2_2") (pintype "passive"))
      (node (ref "C9") (pin "2") (pinfunction "2_2") (pintype "passive"))
      (node (ref "CON1") (pin "P$2") (pinfunction "P$2_P$2") (pintype "bidirectional"))
      (node (ref "HDMI0") (pin "11") (pinfunction "11_11") (pintype "bidirectional"))
      (node (ref "HDMI0") (pin "13") (pinfunction "13_13") (pintype "bidirectional"))
      (node (ref "HDMI0") (pin "14") (pinfunction "14_14") (pintype "bidirectional"))
      (node (ref "HDMI0") (pin "17") (pinfunction "17_17") (pintype "bidirectional"))
      (node (ref "HDMI0") (pin "18") (pinfunction "18_18") (pintype "bidirectional"))
      (node (ref "HDMI0") (pin "19") (pinfunction "19_19") (pintype "bidirectional"))
      (node (ref "HDMI0") (pin "2") (pinfunction "2_2") (pintype "bidirectional"))
      (node (ref "HDMI0") (pin "5") (pinfunction "5_5") (pintype "bidirectional"))
      (node (ref "HDMI0") (pin "8") (pinfunction "8_8") (pintype "bidirectional"))
      (node (ref "HDMI0") (pin "SHELL1") (pinfunction "SHELL1_SHELL1") (pintype "bidirectional"))
      (node (ref "HDMI0") (pin "SHELL2") (pinfunction "SHELL2_SHELL2") (pintype "bidirectional"))
      (node (ref "HDMI0") (pin "SHELL3") (pinfunction "SHELL3_SHELL3") (pintype "bidirectional"))
      (node (ref "HDMI0") (pin "SHELL4") (pinfunction "SHELL4_SHELL4") (pintype "bidirectional"))
      (node (ref "HDMI1") (pin "11") (pinfunction "11_11") (pintype "bidirectional"))
      (node (ref "HDMI1") (pin "13") (pinfunction "13_13") (pintype "bidirectional"))
      (node (ref "HDMI1") (pin "14") (pinfunction "14_14") (pintype "bidirectional"))
      (node (ref "HDMI1") (pin "17") (pinfunction "17_17") (pintype "bidirectional"))
      (node (ref "HDMI1") (pin "18") (pinfunction "18_18") (pintype "bidirectional"))
      (node (ref "HDMI1") (pin "19") (pinfunction "19_19") (pintype "bidirectional"))
      (node (ref "HDMI1") (pin "2") (pinfunction "2_2") (pintype "bidirectional"))
      (node (ref "HDMI1") (pin "5") (pinfunction "5_5") (pintype "bidirectional"))
      (node (ref "HDMI1") (pin "8") (pinfunction "8_8") (pintype "bidirectional"))
      (node (ref "HDMI1") (pin "SHELL1") (pinfunction "SHELL1_SHELL1") (pintype "bidirectional"))
      (node (ref "HDMI1") (pin "SHELL2") (pinfunction "SHELL2_SHELL2") (pintype "bidirectional"))
      (node (ref "HDMI1") (pin "SHELL3") (pinfunction "SHELL3_SHELL3") (pintype "bidirectional"))
      (node (ref "HDMI1") (pin "SHELL4") (pinfunction "SHELL4_SHELL4") (pintype "bidirectional"))
      (node (ref "HDMI2") (pin "11") (pinfunction "11_11") (pintype "bidirectional"))
      (node (ref "HDMI2") (pin "13") (pinfunction "13_13") (pintype "bidirectional"))
      (node (ref "HDMI2") (pin "14") (pinfunction "14_14") (pintype "bidirectional"))
      (node (ref "HDMI2") (pin "17") (pinfunction "17_17") (pintype "bidirectional"))
      (node (ref "HDMI2") (pin "18") (pinfunction "18_18") (pintype "bidirectional"))
      (node (ref "HDMI2") (pin "19") (pinfunction "19_19") (pintype "bidirectional"))
      (node (ref "HDMI2") (pin "2") (pinfunction "2_2") (pintype "bidirectional"))
      (node (ref "HDMI2") (pin "5") (pinfunction "5_5") (pintype "bidirectional"))
      (node (ref "HDMI2") (pin "8") (pinfunction "8_8") (pintype "bidirectional"))
      (node (ref "HDMI2") (pin "SHELL1") (pinfunction "SHELL1_SHELL1") (pintype "bidirectional"))
      (node (ref "HDMI2") (pin "SHELL2") (pinfunction "SHELL2_SHELL2") (pintype "bidirectional"))
      (node (ref "HDMI2") (pin "SHELL3") (pinfunction "SHELL3_SHELL3") (pintype "bidirectional"))
      (node (ref "HDMI2") (pin "SHELL4") (pinfunction "SHELL4_SHELL4") (pintype "bidirectional"))
      (node (ref "HDMI3") (pin "11") (pinfunction "11_11") (pintype "bidirectional"))
      (node (ref "HDMI3") (pin "13") (pinfunction "13_13") (pintype "bidirectional"))
      (node (ref "HDMI3") (pin "14") (pinfunction "14_14") (pintype "bidirectional"))
      (node (ref "HDMI3") (pin "17") (pinfunction "17_17") (pintype "bidirectional"))
      (node (ref "HDMI3") (pin "18") (pinfunction "18_18") (pintype "bidirectional"))
      (node (ref "HDMI3") (pin "19") (pinfunction "19_19") (pintype "bidirectional"))
      (node (ref "HDMI3") (pin "2") (pinfunction "2_2") (pintype "bidirectional"))
      (node (ref "HDMI3") (pin "5") (pinfunction "5_5") (pintype "bidirectional"))
      (node (ref "HDMI3") (pin "8") (pinfunction "8_8") (pintype "bidirectional"))
      (node (ref "HDMI3") (pin "SHELL1") (pinfunction "SHELL1_SHELL1") (pintype "bidirectional"))
      (node (ref "HDMI3") (pin "SHELL2") (pinfunction "SHELL2_SHELL2") (pintype "bidirectional"))
      (node (ref "HDMI3") (pin "SHELL3") (pinfunction "SHELL3_SHELL3") (pintype "bidirectional"))
      (node (ref "HDMI3") (pin "SHELL4") (pinfunction "SHELL4_SHELL4") (pintype "bidirectional"))
      (node (ref "HDMI4") (pin "11") (pinfunction "11_11") (pintype "bidirectional"))
      (node (ref "HDMI4") (pin "13") (pinfunction "13_13") (pintype "bidirectional"))
      (node (ref "HDMI4") (pin "14") (pinfunction "14_14") (pintype "bidirectional"))
      (node (ref "HDMI4") (pin "17") (pinfunction "17_17") (pintype "bidirectional"))
      (node (ref "HDMI4") (pin "18") (pinfunction "18_18") (pintype "bidirectional"))
      (node (ref "HDMI4") (pin "19") (pinfunction "19_19") (pintype "bidirectional"))
      (node (ref "HDMI4") (pin "2") (pinfunction "2_2") (pintype "bidirectional"))
      (node (ref "HDMI4") (pin "5") (pinfunction "5_5") (pintype "bidirectional"))
      (node (ref "HDMI4") (pin "8") (pinfunction "8_8") (pintype "bidirectional"))
      (node (ref "HDMI4") (pin "SHELL1") (pinfunction "SHELL1_SHELL1") (pintype "bidirectional"))
      (node (ref "HDMI4") (pin "SHELL2") (pinfunction "SHELL2_SHELL2") (pintype "bidirectional"))
      (node (ref "HDMI4") (pin "SHELL3") (pinfunction "SHELL3_SHELL3") (pintype "bidirectional"))
      (node (ref "HDMI4") (pin "SHELL4") (pinfunction "SHELL4_SHELL4") (pintype "bidirectional"))
      (node (ref "HDMI5") (pin "11") (pinfunction "11_11") (pintype "bidirectional"))
      (node (ref "HDMI5") (pin "13") (pinfunction "13_13") (pintype "bidirectional"))
      (node (ref "HDMI5") (pin "14") (pinfunction "14_14") (pintype "bidirectional"))
      (node (ref "HDMI5") (pin "17") (pinfunction "17_17") (pintype "bidirectional"))
      (node (ref "HDMI5") (pin "18") (pinfunction "18_18") (pintype "bidirectional"))
      (node (ref "HDMI5") (pin "19") (pinfunction "19_19") (pintype "bidirectional"))
      (node (ref "HDMI5") (pin "2") (pinfunction "2_2") (pintype "bidirectional"))
      (node (ref "HDMI5") (pin "5") (pinfunction "5_5") (pintype "bidirectional"))
      (node (ref "HDMI5") (pin "8") (pinfunction "8_8") (pintype "bidirectional"))
      (node (ref "HDMI5") (pin "SHELL1") (pinfunction "SHELL1_SHELL1") (pintype "bidirectional"))
      (node (ref "HDMI5") (pin "SHELL2") (pinfunction "SHELL2_SHELL2") (pintype "bidirectional"))
      (node (ref "HDMI5") (pin "SHELL3") (pinfunction "SHELL3_SHELL3") (pintype "bidirectional"))
      (node (ref "HDMI5") (pin "SHELL4") (pinfunction "SHELL4_SHELL4") (pintype "bidirectional"))
      (node (ref "HDMI6") (pin "11") (pinfunction "11_11") (pintype "bidirectional"))
      (node (ref "HDMI6") (pin "13") (pinfunction "13_13") (pintype "bidirectional"))
      (node (ref "HDMI6") (pin "14") (pinfunction "14_14") (pintype "bidirectional"))
      (node (ref "HDMI6") (pin "17") (pinfunction "17_17") (pintype "bidirectional"))
      (node (ref "HDMI6") (pin "18") (pinfunction "18_18") (pintype "bidirectional"))
      (node (ref "HDMI6") (pin "19") (pinfunction "19_19") (pintype "bidirectional"))
      (node (ref "HDMI6") (pin "2") (pinfunction "2_2") (pintype "bidirectional"))
      (node (ref "HDMI6") (pin "5") (pinfunction "5_5") (pintype "bidirectional"))
      (node (ref "HDMI6") (pin "8") (pinfunction "8_8") (pintype "bidirectional"))
      (node (ref "HDMI6") (pin "SHELL1") (pinfunction "SHELL1_SHELL1") (pintype "bidirectional"))
      (node (ref "HDMI6") (pin "SHELL2") (pinfunction "SHELL2_SHELL2") (pintype "bidirectional"))
      (node (ref "HDMI6") (pin "SHELL3") (pinfunction "SHELL3_SHELL3") (pintype "bidirectional"))
      (node (ref "HDMI6") (pin "SHELL4") (pinfunction "SHELL4_SHELL4") (pintype "bidirectional"))
      (node (ref "HDMI7") (pin "11") (pinfunction "11_11") (pintype "bidirectional"))
      (node (ref "HDMI7") (pin "13") (pinfunction "13_13") (pintype "bidirectional"))
      (node (ref "HDMI7") (pin "14") (pinfunction "14_14") (pintype "bidirectional"))
      (node (ref "HDMI7") (pin "17") (pinfunction "17_17") (pintype "bidirectional"))
      (node (ref "HDMI7") (pin "18") (pinfunction "18_18") (pintype "bidirectional"))
      (node (ref "HDMI7") (pin "19") (pinfunction "19_19") (pintype "bidirectional"))
      (node (ref "HDMI7") (pin "2") (pinfunction "2_2") (pintype "bidirectional"))
      (node (ref "HDMI7") (pin "5") (pinfunction "5_5") (pintype "bidirectional"))
      (node (ref "HDMI7") (pin "8") (pinfunction "8_8") (pintype "bidirectional"))
      (node (ref "HDMI7") (pin "SHELL1") (pinfunction "SHELL1_SHELL1") (pintype "bidirectional"))
      (node (ref "HDMI7") (pin "SHELL2") (pinfunction "SHELL2_SHELL2") (pintype "bidirectional"))
      (node (ref "HDMI7") (pin "SHELL3") (pinfunction "SHELL3_SHELL3") (pintype "bidirectional"))
      (node (ref "HDMI7") (pin "SHELL4") (pinfunction "SHELL4_SHELL4") (pintype "bidirectional"))
      (node (ref "HDMI8") (pin "11") (pinfunction "11_11") (pintype "bidirectional"))
      (node (ref "HDMI8") (pin "13") (pinfunction "13_13") (pintype "bidirectional"))
      (node (ref "HDMI8") (pin "14") (pinfunction "14_14") (pintype "bidirectional"))
      (node (ref "HDMI8") (pin "17") (pinfunction "17_17") (pintype "bidirectional"))
      (node (ref "HDMI8") (pin "18") (pinfunction "18_18") (pintype "bidirectional"))
      (node (ref "HDMI8") (pin "19") (pinfunction "19_19") (pintype "bidirectional"))
      (node (ref "HDMI8") (pin "2") (pinfunction "2_2") (pintype "bidirectional"))
      (node (ref "HDMI8") (pin "5") (pinfunction "5_5") (pintype "bidirectional"))
      (node (ref "HDMI8") (pin "8") (pinfunction "8_8") (pintype "bidirectional"))
      (node (ref "HDMI8") (pin "SHELL1") (pinfunction "SHELL1_SHELL1") (pintype "bidirectional"))
      (node (ref "HDMI8") (pin "SHELL2") (pinfunction "SHELL2_SHELL2") (pintype "bidirectional"))
      (node (ref "HDMI8") (pin "SHELL3") (pinfunction "SHELL3_SHELL3") (pintype "bidirectional"))
      (node (ref "HDMI8") (pin "SHELL4") (pinfunction "SHELL4_SHELL4") (pintype "bidirectional"))
      (node (ref "HDMI9") (pin "11") (pinfunction "11_11") (pintype "bidirectional"))
      (node (ref "HDMI9") (pin "13") (pinfunction "13_13") (pintype "bidirectional"))
      (node (ref "HDMI9") (pin "14") (pinfunction "14_14") (pintype "bidirectional"))
      (node (ref "HDMI9") (pin "17") (pinfunction "17_17") (pintype "bidirectional"))
      (node (ref "HDMI9") (pin "18") (pinfunction "18_18") (pintype "bidirectional"))
      (node (ref "HDMI9") (pin "19") (pinfunction "19_19") (pintype "bidirectional"))
      (node (ref "HDMI9") (pin "2") (pinfunction "2_2") (pintype "bidirectional"))
      (node (ref "HDMI9") (pin "5") (pinfunction "5_5") (pintype "bidirectional"))
      (node (ref "HDMI9") (pin "8") (pinfunction "8_8") (pintype "bidirectional"))
      (node (ref "HDMI9") (pin "SHELL1") (pinfunction "SHELL1_SHELL1") (pintype "bidirectional"))
      (node (ref "HDMI9") (pin "SHELL2") (pinfunction "SHELL2_SHELL2") (pintype "bidirectional"))
      (node (ref "HDMI9") (pin "SHELL3") (pinfunction "SHELL3_SHELL3") (pintype "bidirectional"))
      (node (ref "HDMI9") (pin "SHELL4") (pinfunction "SHELL4_SHELL4") (pintype "bidirectional"))
      (node (ref "IC1") (pin "12") (pinfunction "~{EN}_12") (pintype "input"))
      (node (ref "IC1") (pin "8") (pinfunction "GND_8") (pintype "passive"))
      (node (ref "IC10") (pin "2") (pinfunction "GND_2") (pintype "passive"))
      (node (ref "IC11") (pin "12") (pinfunction "~{EN}_12") (pintype "input"))
      (node (ref "IC11") (pin "8") (pinfunction "GND_8") (pintype "passive"))
      (node (ref "IC12") (pin "2") (pinfunction "GND_2") (pintype "passive"))
      (node (ref "IC13") (pin "12") (pinfunction "~{EN}_12") (pintype "input"))
      (node (ref "IC13") (pin "8") (pinfunction "GND_8") (pintype "passive"))
      (node (ref "IC14") (pin "2") (pinfunction "GND_2") (pintype "passive"))
      (node (ref "IC15") (pin "12") (pinfunction "~{EN}_12") (pintype "input"))
      (node (ref "IC15") (pin "8") (pinfunction "GND_8") (pintype "passive"))
      (node (ref "IC16") (pin "2") (pinfunction "GND_2") (pintype "passive"))
      (node (ref "IC17") (pin "12") (pinfunction "~{EN}_12") (pintype "input"))
      (node (ref "IC17") (pin "8") (pinfunction "GND_8") (pintype "passive"))
      (node (ref "IC18") (pin "2") (pinfunction "GND_2") (pintype "passive"))
      (node (ref "IC19") (pin "12") (pinfunction "~{EN}_12") (pintype "input"))
      (node (ref "IC19") (pin "8") (pinfunction "GND_8") (pintype "passive"))
      (node (ref "IC2") (pin "2") (pinfunction "GND_2") (pintype "passive"))
      (node (ref "IC20") (pin "2") (pinfunction "GND_2") (pintype "passive"))
      (node (ref "IC21") (pin "7") (pinfunction "VEE_7") (pintype "bidirectional"))
      (node (ref "IC21") (pin "8") (pinfunction "GND_8") (pintype "bidirectional"))
      (node (ref "IC22") (pin "7") (pinfunction "VEE_7") (pintype "bidirectional"))
      (node (ref "IC22") (pin "8") (pinfunction "GND_8") (pintype "bidirectional"))
      (node (ref "IC23") (pin "7") (pinfunction "VEE_7") (pintype "bidirectional"))
      (node (ref "IC23") (pin "8") (pinfunction "GND_8") (pintype "bidirectional"))
      (node (ref "IC24") (pin "7") (pinfunction "VEE_7") (pintype "bidirectional"))
      (node (ref "IC24") (pin "8") (pinfunction "GND_8") (pintype "bidirectional"))
      (node (ref "IC25") (pin "7") (pinfunction "VEE_7") (pintype "bidirectional"))
      (node (ref "IC25") (pin "8") (pinfunction "GND_8") (pintype "bidirectional"))
      (node (ref "IC26") (pin "7") (pinfunction "VEE_7") (pintype "bidirectional"))
      (node (ref "IC26") (pin "8") (pinfunction "GND_8") (pintype "bidirectional"))
      (node (ref "IC27") (pin "7") (pinfunction "VEE_7") (pintype "bidirectional"))
      (node (ref "IC27") (pin "8") (pinfunction "GND_8") (pintype "bidirectional"))
      (node (ref "IC28") (pin "7") (pinfunction "VEE_7") (pintype "bidirectional"))
      (node (ref "IC28") (pin "8") (pinfunction "GND_8") (pintype "bidirectional"))
      (node (ref "IC29") (pin "GND") (pinfunction "GND_GND") (pintype "input"))
      (node (ref "IC3") (pin "12") (pinfunction "~{EN}_12") (pintype "input"))
      (node (ref "IC3") (pin "8") (pinfunction "GND_8") (pintype "passive"))
      (node (ref "IC30") (pin "3") (pinfunction "GND_3") (pintype "passive"))
      (node (ref "IC4") (pin "2") (pinfunction "GND_2") (pintype "passive"))
      (node (ref "IC5") (pin "12") (pinfunction "~{EN}_12") (pintype "input"))
      (node (ref "IC5") (pin "8") (pinfunction "GND_8") (pintype "passive"))
      (node (ref "IC6") (pin "2") (pinfunction "GND_2") (pintype "passive"))
      (node (ref "IC7") (pin "12") (pinfunction "~{EN}_12") (pintype "input"))
      (node (ref "IC7") (pin "8") (pinfunction "GND_8") (pintype "passive"))
      (node (ref "IC8") (pin "2") (pinfunction "GND_2") (pintype "passive"))
      (node (ref "IC9") (pin "12") (pinfunction "~{EN}_12") (pintype "input"))
      (node (ref "IC9") (pin "8") (pinfunction "GND_8") (pintype "passive"))
      (node (ref "JP1") (pin "1") (pinfunction "1_1") (pintype "passive"))
      (node (ref "JP10") (pin "1") (pinfunction "1_1") (pintype "passive"))
      (node (ref "JP11") (pin "1") (pinfunction "1_1") (pintype "passive"))
      (node (ref "JP12") (pin "1") (pinfunction "1_1") (pintype "passive"))
      (node (ref "JP13") (pin "1") (pinfunction "1_1") (pintype "passive"))
      (node (ref "JP2") (pin "1") (pinfunction "1_1") (pintype "passive"))
      (node (ref "JP3") (pin "1") (pinfunction "1_1") (pintype "passive"))
      (node (ref "JP4") (pin "1") (pinfunction "1_1") (pintype "passive"))
      (node (ref "JP5") (pin "1") (pinfunction "1_1") (pintype "passive"))
      (node (ref "JP6") (pin "1") (pinfunction "1_1") (pintype "passive"))
      (node (ref "JP7") (pin "1") (pinfunction "1_1") (pintype "passive"))
      (node (ref "JP8") (pin "1") (pinfunction "1_1") (pintype "passive"))
      (node (ref "JP9") (pin "1") (pinfunction "1_1") (pintype "passive"))
      (node (ref "MOD1") (pin "1") (pinfunction "GND_1") (pintype "bidirectional"))
      (node (ref "MOD1") (pin "10") (pinfunction "GND2_10") (pintype "bidirectional"))
      (node (ref "R10") (pin "1") (pinfunction "1_1") (pintype "passive"))
      (node (ref "R2") (pin "1") (pinfunction "1_1") (pintype "passive"))
      (node (ref "R25") (pin "1") (pinfunction "1_1") (pintype "passive"))
      (node (ref "R31") (pin "1") (pinfunction "1_1") (pintype "passive"))
      (node (ref "R33") (pin "1") (pinfunction "1_1") (pintype "passive"))
      (node (ref "R35") (pin "1") (pinfunction "1_1") (pintype "passive"))
      (node (ref "R37") (pin "1") (pinfunction "1_1") (pintype "passive"))
      (node (ref "R39") (pin "1") (pinfunction "1_1") (pintype "passive"))
      (node (ref "R4") (pin "1") (pinfunction "1_1") (pintype "passive"))
      (node (ref "R41") (pin "1") (pinfunction "1_1") (pintype "passive"))
      (node (ref "R43") (pin "1") (pinfunction "1_1") (pintype "passive"))
      (node (ref "R45") (pin "1") (pinfunction "1_1") (pintype "passive"))
      (node (ref "R47") (pin "1") (pinfunction "1_1") (pintype "passive"))
      (node (ref "R49") (pin "1") (pinfunction "1_1") (pintype "passive"))
      (node (ref "R51") (pin "1") (pinfunction "1_1") (pintype "passive"))
      (node (ref "R53") (pin "1") (pinfunction "1_1") (pintype "passive"))
      (node (ref "R55") (pin "1") (pinfunction "1_1") (pintype "passive"))
      (node (ref "R57") (pin "1") (pinfunction "1_1") (pintype "passive"))
      (node (ref "R59") (pin "1") (pinfunction "1_1") (pintype "passive"))
      (node (ref "R6") (pin "1") (pinfunction "1_1") (pintype "passive"))
      (node (ref "R61") (pin "1") (pinfunction "1_1") (pintype "passive"))
      (node (ref "R63") (pin "1") (pinfunction "1_1") (pintype "passive"))
      (node (ref "R65") (pin "1") (pinfunction "1_1") (pintype "passive"))
      (node (ref "R67") (pin "1") (pinfunction "1_1") (pintype "passive"))
      (node (ref "R69") (pin "1") (pinfunction "1_1") (pintype "passive"))
      (node (ref "R71") (pin "1") (pinfunction "1_1") (pintype "passive"))
      (node (ref "R73") (pin "1") (pinfunction "1_1") (pintype "passive"))
      (node (ref "R75") (pin "1") (pinfunction "1_1") (pintype "passive"))
      (node (ref "R77") (pin "1") (pinfunction "1_1") (pintype "passive"))
      (node (ref "R79") (pin "1") (pinfunction "1_1") (pintype "passive"))
      (node (ref "R8") (pin "1") (pinfunction "1_1") (pintype "passive"))
      (node (ref "SJ1") (pin "2") (pinfunction "2_2") (pintype "passive"))
      (node (ref "SJ10") (pin "2") (pinfunction "2_2") (pintype "passive"))
      (node (ref "SJ11") (pin "2") (pinfunction "2_2") (pintype "passive"))
      (node (ref "SJ12") (pin "2") (pinfunction "2_2") (pintype "passive"))
      (node (ref "SJ2") (pin "2") (pinfunction "2_2") (pintype "passive"))
      (node (ref "SJ3") (pin "1") (pinfunction "1_1") (pintype "passive"))
      (node (ref "SJ4") (pin "1") (pinfunction "1_1") (pintype "passive"))
      (node (ref "SJ5") (pin "1") (pinfunction "1_1") (pintype "passive"))
      (node (ref "SJ6") (pin "2") (pinfunction "2_2") (pintype "passive"))
      (node (ref "SJ7") (pin "2") (pinfunction "2_2") (pintype "passive"))
      (node (ref "SJ8") (pin "2") (pinfunction "2_2") (pintype "passive"))
      (node (ref "SJ9") (pin "2") (pinfunction "2_2") (pintype "passive"))
      (node (ref "TP2") (pin "P$1") (pinfunction "1_P$1") (pintype "bidirectional"))
    )
    (net (code "111") (name "Net-(D1-PadA)") (class "Default")
      (node (ref "D1") (pin "A") (pinfunction "A_A") (pintype "passive"))
      (node (ref "R21") (pin "1") (pinfunction "1_1") (pintype "passive"))
    )
    (net (code "112") (name "Net-(D1-PadC)") (class "Default")
      (node (ref "D1") (pin "C") (pinfunction "C_C") (pintype "passive"))
      (node (ref "D2") (pin "C") (pinfunction "C_C") (pintype "passive"))
      (node (ref "D3") (pin "C") (pinfunction "C_C") (pintype "passive"))
      (node (ref "D4") (pin "C") (pinfunction "C_C") (pintype "passive"))
      (node (ref "SJ11") (pin "1") (pinfunction "1_1") (pintype "passive"))
    )
    (net (code "113") (name "Net-(D2-PadA)") (class "Default")
      (node (ref "D2") (pin "A") (pinfunction "A_A") (pintype "passive"))
      (node (ref "R22") (pin "1") (pinfunction "1_1") (pintype "passive"))
    )
    (net (code "114") (name "Net-(D3-PadA)") (class "Default")
      (node (ref "D3") (pin "A") (pinfunction "A_A") (pintype "passive"))
      (node (ref "R23") (pin "1") (pinfunction "1_1") (pintype "passive"))
    )
    (net (code "115") (name "Net-(D4-PadA)") (class "Default")
      (node (ref "D4") (pin "A") (pinfunction "A_A") (pintype "passive"))
      (node (ref "R24") (pin "1") (pinfunction "1_1") (pintype "passive"))
    )
    (net (code "116") (name "Net-(D5-PadA)") (class "Default")
      (node (ref "D5") (pin "A") (pinfunction "A_A") (pintype "passive"))
      (node (ref "R26") (pin "1") (pinfunction "1_1") (pintype "passive"))
    )
    (net (code "117") (name "Net-(D5-PadC)") (class "Default")
      (node (ref "D5") (pin "C") (pinfunction "C_C") (pintype "passive"))
      (node (ref "D6") (pin "C") (pinfunction "C_C") (pintype "passive"))
      (node (ref "D7") (pin "C") (pinfunction "C_C") (pintype "passive"))
      (node (ref "D8") (pin "C") (pinfunction "C_C") (pintype "passive"))
      (node (ref "SJ12") (pin "1") (pinfunction "1_1") (pintype "passive"))
    )
    (net (code "118") (name "Net-(D6-PadA)") (class "Default")
      (node (ref "D6") (pin "A") (pinfunction "A_A") (pintype "passive"))
      (node (ref "R27") (pin "1") (pinfunction "1_1") (pintype "passive"))
    )
    (net (code "119") (name "Net-(D7-PadA)") (class "Default")
      (node (ref "D7") (pin "A") (pinfunction "A_A") (pintype "passive"))
      (node (ref "R28") (pin "1") (pinfunction "1_1") (pintype "passive"))
    )
    (net (code "120") (name "Net-(D8-PadA)") (class "Default")
      (node (ref "D8") (pin "A") (pinfunction "A_A") (pintype "passive"))
      (node (ref "R29") (pin "1") (pinfunction "1_1") (pintype "passive"))
    )
    (net (code "121") (name "Net-(D9-PadC)") (class "Default")
      (node (ref "D9") (pin "C") (pinfunction "C_C") (pintype "passive"))
      (node (ref "SJ13") (pin "1") (pinfunction "1_1") (pintype "passive"))
    )
    (net (code "122") (name "Net-(IC3-DOUT1+)") (class "Default")
      (node (ref "HDMI1") (pin "4") (pinfunction "4_4") (pintype "bidirectional"))
      (node (ref "IC3") (pin "2") (pinfunction "DOUT1+_2") (pintype "output"))
    )
    (net (code "123") (name "Net-(IC3-DOUT1-)") (class "Default")
      (node (ref "HDMI1") (pin "6") (pinfunction "6_6") (pintype "bidirectional"))
      (node (ref "IC3") (pin "3") (pinfunction "DOUT1-_3") (pintype "output"))
    )
    (net (code "124") (name "Net-(IC3-DOUT2+)") (class "Default")
      (node (ref "HDMI1") (pin "7") (pinfunction "7_7") (pintype "bidirectional"))
      (node (ref "IC3") (pin "6") (pinfunction "DOUT2+_6") (pintype "output"))
    )
    (net (code "125") (name "Net-(IC3-DOUT2-)") (class "Default")
      (node (ref "HDMI1") (pin "9") (pinfunction "9_9") (pintype "bidirectional"))
      (node (ref "IC3") (pin "5") (pinfunction "DOUT2-_5") (pintype "output"))
    )
    (net (code "126") (name "Net-(IC3-DOUT3+)") (class "Default")
      (node (ref "HDMI1") (pin "10") (pinfunction "10_10") (pintype "bidirectional"))
      (node (ref "IC3") (pin "10") (pinfunction "DOUT3+_10") (pintype "output"))
    )
    (net (code "127") (name "Net-(IC3-DOUT3-)") (class "Default")
      (node (ref "HDMI1") (pin "12") (pinfunction "12_12") (pintype "bidirectional"))
      (node (ref "IC3") (pin "11") (pinfunction "DOUT3-_11") (pintype "output"))
    )
    (net (code "128") (name "Net-(IC3-DOUT4+)") (class "Default")
      (node (ref "HDMI1") (pin "15") (pinfunction "15_15") (pintype "bidirectional"))
      (node (ref "IC3") (pin "14") (pinfunction "DOUT4+_14") (pintype "output"))
    )
    (net (code "129") (name "Net-(IC3-DOUT4-)") (class "Default")
      (node (ref "HDMI1") (pin "16") (pinfunction "16_16") (pintype "bidirectional"))
      (node (ref "IC3") (pin "13") (pinfunction "DOUT4-_13") (pintype "output"))
    )
    (net (code "130") (name "Net-(IC5-DOUT1+)") (class "Default")
      (node (ref "HDMI2") (pin "4") (pinfunction "4_4") (pintype "bidirectional"))
      (node (ref "IC5") (pin "2") (pinfunction "DOUT1+_2") (pintype "output"))
    )
    (net (code "131") (name "Net-(IC5-DOUT1-)") (class "Default")
      (node (ref "HDMI2") (pin "6") (pinfunction "6_6") (pintype "bidirectional"))
      (node (ref "IC5") (pin "3") (pinfunction "DOUT1-_3") (pintype "output"))
    )
    (net (code "132") (name "Net-(IC5-DOUT2+)") (class "Default")
      (node (ref "HDMI2") (pin "7") (pinfunction "7_7") (pintype "bidirectional"))
      (node (ref "IC5") (pin "6") (pinfunction "DOUT2+_6") (pintype "output"))
    )
    (net (code "133") (name "Net-(IC5-DOUT2-)") (class "Default")
      (node (ref "HDMI2") (pin "9") (pinfunction "9_9") (pintype "bidirectional"))
      (node (ref "IC5") (pin "5") (pinfunction "DOUT2-_5") (pintype "output"))
    )
    (net (code "134") (name "Net-(IC5-DOUT3+)") (class "Default")
      (node (ref "HDMI2") (pin "10") (pinfunction "10_10") (pintype "bidirectional"))
      (node (ref "IC5") (pin "10") (pinfunction "DOUT3+_10") (pintype "output"))
    )
    (net (code "135") (name "Net-(IC5-DOUT3-)") (class "Default")
      (node (ref "HDMI2") (pin "12") (pinfunction "12_12") (pintype "bidirectional"))
      (node (ref "IC5") (pin "11") (pinfunction "DOUT3-_11") (pintype "output"))
    )
    (net (code "136") (name "Net-(IC5-DOUT4+)") (class "Default")
      (node (ref "HDMI2") (pin "15") (pinfunction "15_15") (pintype "bidirectional"))
      (node (ref "IC5") (pin "14") (pinfunction "DOUT4+_14") (pintype "output"))
    )
    (net (code "137") (name "Net-(IC5-DOUT4-)") (class "Default")
      (node (ref "HDMI2") (pin "16") (pinfunction "16_16") (pintype "bidirectional"))
      (node (ref "IC5") (pin "13") (pinfunction "DOUT4-_13") (pintype "output"))
    )
    (net (code "138") (name "Net-(IC7-DOUT1+)") (class "Default")
      (node (ref "HDMI3") (pin "4") (pinfunction "4_4") (pintype "bidirectional"))
      (node (ref "IC7") (pin "2") (pinfunction "DOUT1+_2") (pintype "output"))
    )
    (net (code "139") (name "Net-(IC7-DOUT1-)") (class "Default")
      (node (ref "HDMI3") (pin "6") (pinfunction "6_6") (pintype "bidirectional"))
      (node (ref "IC7") (pin "3") (pinfunction "DOUT1-_3") (pintype "output"))
    )
    (net (code "140") (name "Net-(IC7-DOUT2+)") (class "Default")
      (node (ref "HDMI3") (pin "7") (pinfunction "7_7") (pintype "bidirectional"))
      (node (ref "IC7") (pin "6") (pinfunction "DOUT2+_6") (pintype "output"))
    )
    (net (code "141") (name "Net-(IC7-DOUT2-)") (class "Default")
      (node (ref "HDMI3") (pin "9") (pinfunction "9_9") (pintype "bidirectional"))
      (node (ref "IC7") (pin "5") (pinfunction "DOUT2-_5") (pintype "output"))
    )
    (net (code "142") (name "Net-(IC7-DOUT3+)") (class "Default")
      (node (ref "HDMI3") (pin "10") (pinfunction "10_10") (pintype "bidirectional"))
      (node (ref "IC7") (pin "10") (pinfunction "DOUT3+_10") (pintype "output"))
    )
    (net (code "143") (name "Net-(IC7-DOUT3-)") (class "Default")
      (node (ref "HDMI3") (pin "12") (pinfunction "12_12") (pintype "bidirectional"))
      (node (ref "IC7") (pin "11") (pinfunction "DOUT3-_11") (pintype "output"))
    )
    (net (code "144") (name "Net-(IC7-DOUT4+)") (class "Default")
      (node (ref "HDMI3") (pin "15") (pinfunction "15_15") (pintype "bidirectional"))
      (node (ref "IC7") (pin "14") (pinfunction "DOUT4+_14") (pintype "output"))
    )
    (net (code "145") (name "Net-(IC7-DOUT4-)") (class "Default")
      (node (ref "HDMI3") (pin "16") (pinfunction "16_16") (pintype "bidirectional"))
      (node (ref "IC7") (pin "13") (pinfunction "DOUT4-_13") (pintype "output"))
    )
    (net (code "146") (name "Net-(IC9-DOUT1+)") (class "Default")
      (node (ref "HDMI4") (pin "4") (pinfunction "4_4") (pintype "bidirectional"))
      (node (ref "IC9") (pin "2") (pinfunction "DOUT1+_2") (pintype "output"))
    )
    (net (code "147") (name "Net-(IC9-DOUT1-)") (class "Default")
      (node (ref "HDMI4") (pin "6") (pinfunction "6_6") (pintype "bidirectional"))
      (node (ref "IC9") (pin "3") (pinfunction "DOUT1-_3") (pintype "output"))
    )
    (net (code "148") (name "Net-(IC9-DOUT2+)") (class "Default")
      (node (ref "HDMI4") (pin "7") (pinfunction "7_7") (pintype "bidirectional"))
      (node (ref "IC9") (pin "6") (pinfunction "DOUT2+_6") (pintype "output"))
    )
    (net (code "149") (name "Net-(IC9-DOUT2-)") (class "Default")
      (node (ref "HDMI4") (pin "9") (pinfunction "9_9") (pintype "bidirectional"))
      (node (ref "IC9") (pin "5") (pinfunction "DOUT2-_5") (pintype "output"))
    )
    (net (code "150") (name "Net-(IC9-DOUT3+)") (class "Default")
      (node (ref "HDMI4") (pin "10") (pinfunction "10_10") (pintype "bidirectional"))
      (node (ref "IC9") (pin "10") (pinfunction "DOUT3+_10") (pintype "output"))
    )
    (net (code "151") (name "Net-(IC9-DOUT3-)") (class "Default")
      (node (ref "HDMI4") (pin "12") (pinfunction "12_12") (pintype "bidirectional"))
      (node (ref "IC9") (pin "11") (pinfunction "DOUT3-_11") (pintype "output"))
    )
    (net (code "152") (name "Net-(IC9-DOUT4+)") (class "Default")
      (node (ref "HDMI4") (pin "15") (pinfunction "15_15") (pintype "bidirectional"))
      (node (ref "IC9") (pin "14") (pinfunction "DOUT4+_14") (pintype "output"))
    )
    (net (code "153") (name "Net-(IC9-DOUT4-)") (class "Default")
      (node (ref "HDMI4") (pin "16") (pinfunction "16_16") (pintype "bidirectional"))
      (node (ref "IC9") (pin "13") (pinfunction "DOUT4-_13") (pintype "output"))
    )
    (net (code "154") (name "Net-(IC11-DOUT1+)") (class "Default")
      (node (ref "HDMI5") (pin "4") (pinfunction "4_4") (pintype "bidirectional"))
      (node (ref "IC11") (pin "2") (pinfunction "DOUT1+_2") (pintype "output"))
    )
    (net (code "155") (name "Net-(IC11-DOUT1-)") (class "Default")
      (node (ref "HDMI5") (pin "6") (pinfunction "6_6") (pintype "bidirectional"))
      (node (ref "IC11") (pin "3") (pinfunction "DOUT1-_3") (pintype "output"))
    )
    (net (code "156") (name "Net-(IC11-DOUT2+)") (class "Default")
      (node (ref "HDMI5") (pin "7") (pinfunction "7_7") (pintype "bidirectional"))
      (node (ref "IC11") (pin "6") (pinfunction "DOUT2+_6") (pintype "output"))
    )
    (net (code "157") (name "Net-(IC11-DOUT2-)") (class "Default")
      (node (ref "HDMI5") (pin "9") (pinfunction "9_9") (pintype "bidirectional"))
      (node (ref "IC11") (pin "5") (pinfunction "DOUT2-_5") (pintype "output"))
    )
    (net (code "158") (name "Net-(IC11-DOUT3+)") (class "Default")
      (node (ref "HDMI5") (pin "10") (pinfunction "10_10") (pintype "bidirectional"))
      (node (ref "IC11") (pin "10") (pinfunction "DOUT3+_10") (pintype "output"))
    )
    (net (code "159") (name "Net-(IC11-DOUT3-)") (class "Default")
      (node (ref "HDMI5") (pin "12") (pinfunction "12_12") (pintype "bidirectional"))
      (node (ref "IC11") (pin "11") (pinfunction "DOUT3-_11") (pintype "output"))
    )
    (net (code "160") (name "Net-(IC11-DOUT4+)") (class "Default")
      (node (ref "HDMI5") (pin "15") (pinfunction "15_15") (pintype "bidirectional"))
      (node (ref "IC11") (pin "14") (pinfunction "DOUT4+_14") (pintype "output"))
    )
    (net (code "161") (name "Net-(IC11-DOUT4-)") (class "Default")
      (node (ref "HDMI5") (pin "16") (pinfunction "16_16") (pintype "bidirectional"))
      (node (ref "IC11") (pin "13") (pinfunction "DOUT4-_13") (pintype "output"))
    )
    (net (code "162") (name "Net-(IC13-DOUT1+)") (class "Default")
      (node (ref "HDMI6") (pin "4") (pinfunction "4_4") (pintype "bidirectional"))
      (node (ref "IC13") (pin "2") (pinfunction "DOUT1+_2") (pintype "output"))
    )
    (net (code "163") (name "Net-(IC13-DOUT1-)") (class "Default")
      (node (ref "HDMI6") (pin "6") (pinfunction "6_6") (pintype "bidirectional"))
      (node (ref "IC13") (pin "3") (pinfunction "DOUT1-_3") (pintype "output"))
    )
    (net (code "164") (name "Net-(IC13-DOUT2+)") (class "Default")
      (node (ref "HDMI6") (pin "7") (pinfunction "7_7") (pintype "bidirectional"))
      (node (ref "IC13") (pin "6") (pinfunction "DOUT2+_6") (pintype "output"))
    )
    (net (code "165") (name "Net-(IC13-DOUT2-)") (class "Default")
      (node (ref "HDMI6") (pin "9") (pinfunction "9_9") (pintype "bidirectional"))
      (node (ref "IC13") (pin "5") (pinfunction "DOUT2-_5") (pintype "output"))
    )
    (net (code "166") (name "Net-(IC13-DOUT3+)") (class "Default")
      (node (ref "HDMI6") (pin "10") (pinfunction "10_10") (pintype "bidirectional"))
      (node (ref "IC13") (pin "10") (pinfunction "DOUT3+_10") (pintype "output"))
    )
    (net (code "167") (name "Net-(IC13-DOUT3-)") (class "Default")
      (node (ref "HDMI6") (pin "12") (pinfunction "12_12") (pintype "bidirectional"))
      (node (ref "IC13") (pin "11") (pinfunction "DOUT3-_11") (pintype "output"))
    )
    (net (code "168") (name "Net-(IC13-DOUT4+)") (class "Default")
      (node (ref "HDMI6") (pin "15") (pinfunction "15_15") (pintype "bidirectional"))
      (node (ref "IC13") (pin "14") (pinfunction "DOUT4+_14") (pintype "output"))
    )
    (net (code "169") (name "Net-(IC13-DOUT4-)") (class "Default")
      (node (ref "HDMI6") (pin "16") (pinfunction "16_16") (pintype "bidirectional"))
      (node (ref "IC13") (pin "13") (pinfunction "DOUT4-_13") (pintype "output"))
    )
    (net (code "170") (name "Net-(IC15-DOUT1+)") (class "Default")
      (node (ref "HDMI7") (pin "4") (pinfunction "4_4") (pintype "bidirectional"))
      (node (ref "IC15") (pin "2") (pinfunction "DOUT1+_2") (pintype "output"))
    )
    (net (code "171") (name "Net-(IC15-DOUT1-)") (class "Default")
      (node (ref "HDMI7") (pin "6") (pinfunction "6_6") (pintype "bidirectional"))
      (node (ref "IC15") (pin "3") (pinfunction "DOUT1-_3") (pintype "output"))
    )
    (net (code "172") (name "Net-(IC15-DOUT2+)") (class "Default")
      (node (ref "HDMI7") (pin "7") (pinfunction "7_7") (pintype "bidirectional"))
      (node (ref "IC15") (pin "6") (pinfunction "DOUT2+_6") (pintype "output"))
    )
    (net (code "173") (name "Net-(IC15-DOUT2-)") (class "Default")
      (node (ref "HDMI7") (pin "9") (pinfunction "9_9") (pintype "bidirectional"))
      (node (ref "IC15") (pin "5") (pinfunction "DOUT2-_5") (pintype "output"))
    )
    (net (code "174") (name "Net-(IC15-DOUT3+)") (class "Default")
      (node (ref "HDMI7") (pin "10") (pinfunction "10_10") (pintype "bidirectional"))
      (node (ref "IC15") (pin "10") (pinfunction "DOUT3+_10") (pintype "output"))
    )
    (net (code "175") (name "Net-(IC15-DOUT3-)") (class "Default")
      (node (ref "HDMI7") (pin "12") (pinfunction "12_12") (pintype "bidirectional"))
      (node (ref "IC15") (pin "11") (pinfunction "DOUT3-_11") (pintype "output"))
    )
    (net (code "176") (name "Net-(IC15-DOUT4+)") (class "Default")
      (node (ref "HDMI7") (pin "15") (pinfunction "15_15") (pintype "bidirectional"))
      (node (ref "IC15") (pin "14") (pinfunction "DOUT4+_14") (pintype "output"))
    )
    (net (code "177") (name "Net-(IC15-DOUT4-)") (class "Default")
      (node (ref "HDMI7") (pin "16") (pinfunction "16_16") (pintype "bidirectional"))
      (node (ref "IC15") (pin "13") (pinfunction "DOUT4-_13") (pintype "output"))
    )
    (net (code "178") (name "Net-(IC17-DOUT1+)") (class "Default")
      (node (ref "HDMI8") (pin "4") (pinfunction "4_4") (pintype "bidirectional"))
      (node (ref "IC17") (pin "2") (pinfunction "DOUT1+_2") (pintype "output"))
    )
    (net (code "179") (name "Net-(IC17-DOUT1-)") (class "Default")
      (node (ref "HDMI8") (pin "6") (pinfunction "6_6") (pintype "bidirectional"))
      (node (ref "IC17") (pin "3") (pinfunction "DOUT1-_3") (pintype "output"))
    )
    (net (code "180") (name "Net-(IC17-DOUT2+)") (class "Default")
      (node (ref "HDMI8") (pin "7") (pinfunction "7_7") (pintype "bidirectional"))
      (node (ref "IC17") (pin "6") (pinfunction "DOUT2+_6") (pintype "output"))
    )
    (net (code "181") (name "Net-(IC17-DOUT2-)") (class "Default")
      (node (ref "HDMI8") (pin "9") (pinfunction "9_9") (pintype "bidirectional"))
      (node (ref "IC17") (pin "5") (pinfunction "DOUT2-_5") (pintype "output"))
    )
    (net (code "182") (name "Net-(IC17-DOUT3+)") (class "Default")
      (node (ref "HDMI8") (pin "10") (pinfunction "10_10") (pintype "bidirectional"))
      (node (ref "IC17") (pin "10") (pinfunction "DOUT3+_10") (pintype "output"))
    )
    (net (code "183") (name "Net-(IC17-DOUT3-)") (class "Default")
      (node (ref "HDMI8") (pin "12") (pinfunction "12_12") (pintype "bidirectional"))
      (node (ref "IC17") (pin "11") (pinfunction "DOUT3-_11") (pintype "output"))
    )
    (net (code "184") (name "Net-(IC17-DOUT4+)") (class "Default")
      (node (ref "HDMI8") (pin "15") (pinfunction "15_15") (pintype "bidirectional"))
      (node (ref "IC17") (pin "14") (pinfunction "DOUT4+_14") (pintype "output"))
    )
    (net (code "185") (name "Net-(IC17-DOUT4-)") (class "Default")
      (node (ref "HDMI8") (pin "16") (pinfunction "16_16") (pintype "bidirectional"))
      (node (ref "IC17") (pin "13") (pinfunction "DOUT4-_13") (pintype "output"))
    )
    (net (code "186") (name "Net-(IC19-DOUT1+)") (class "Default")
      (node (ref "HDMI9") (pin "4") (pinfunction "4_4") (pintype "bidirectional"))
      (node (ref "IC19") (pin "2") (pinfunction "DOUT1+_2") (pintype "output"))
    )
    (net (code "187") (name "Net-(IC19-DOUT1-)") (class "Default")
      (node (ref "HDMI9") (pin "6") (pinfunction "6_6") (pintype "bidirectional"))
      (node (ref "IC19") (pin "3") (pinfunction "DOUT1-_3") (pintype "output"))
    )
    (net (code "188") (name "Net-(IC19-DOUT2+)") (class "Default")
      (node (ref "HDMI9") (pin "7") (pinfunction "7_7") (pintype "bidirectional"))
      (node (ref "IC19") (pin "6") (pinfunction "DOUT2+_6") (pintype "output"))
    )
    (net (code "189") (name "Net-(IC19-DOUT2-)") (class "Default")
      (node (ref "HDMI9") (pin "9") (pinfunction "9_9") (pintype "bidirectional"))
      (node (ref "IC19") (pin "5") (pinfunction "DOUT2-_5") (pintype "output"))
    )
    (net (code "190") (name "Net-(IC19-DOUT3+)") (class "Default")
      (node (ref "HDMI9") (pin "10") (pinfunction "10_10") (pintype "bidirectional"))
      (node (ref "IC19") (pin "10") (pinfunction "DOUT3+_10") (pintype "output"))
    )
    (net (code "191") (name "Net-(IC19-DOUT3-)") (class "Default")
      (node (ref "HDMI9") (pin "12") (pinfunction "12_12") (pintype "bidirectional"))
      (node (ref "IC19") (pin "11") (pinfunction "DOUT3-_11") (pintype "output"))
    )
    (net (code "192") (name "Net-(IC19-DOUT4+)") (class "Default")
      (node (ref "HDMI9") (pin "15") (pinfunction "15_15") (pintype "bidirectional"))
      (node (ref "IC19") (pin "14") (pinfunction "DOUT4+_14") (pintype "output"))
    )
    (net (code "193") (name "Net-(IC19-DOUT4-)") (class "Default")
      (node (ref "HDMI9") (pin "16") (pinfunction "16_16") (pintype "bidirectional"))
      (node (ref "IC19") (pin "13") (pinfunction "DOUT4-_13") (pintype "output"))
    )
    (net (code "194") (name "Net-(R25-Pad2)") (class "Default")
      (node (ref "R25") (pin "2") (pinfunction "2_2") (pintype "passive"))
      (node (ref "SJ13") (pin "2") (pinfunction "2_2") (pintype "passive"))
    )
    (net (code "195") (name "unconnected-(IC22-Y2-Pad15)") (class "Default")
      (node (ref "IC22") (pin "15") (pinfunction "Y2_15") (pintype "bidirectional"))
    )
    (net (code "196") (name "unconnected-(IC22-Y3-Pad12)") (class "Default")
      (node (ref "IC22") (pin "12") (pinfunction "Y3_12") (pintype "bidirectional"))
    )
    (net (code "197") (name "unconnected-(IC22-Y4-Pad1)") (class "Default")
      (node (ref "IC22") (pin "1") (pinfunction "Y4_1") (pintype "bidirectional"))
    )
    (net (code "198") (name "unconnected-(IC22-Y5-Pad5)") (class "Default")
      (node (ref "IC22") (pin "5") (pinfunction "Y5_5") (pintype "bidirectional"))
    )
    (net (code "199") (name "unconnected-(IC22-Y6-Pad2)") (class "Default")
      (node (ref "IC22") (pin "2") (pinfunction "Y6_2") (pintype "bidirectional"))
    )
    (net (code "200") (name "unconnected-(IC22-Y7-Pad4)") (class "Default")
      (node (ref "IC22") (pin "4") (pinfunction "Y7_4") (pintype "bidirectional"))
    )
    (net (code "201") (name "unconnected-(IC24-Y2-Pad15)") (class "Default")
      (node (ref "IC24") (pin "15") (pinfunction "Y2_15") (pintype "bidirectional"))
    )
    (net (code "202") (name "unconnected-(IC24-Y3-Pad12)") (class "Default")
      (node (ref "IC24") (pin "12") (pinfunction "Y3_12") (pintype "bidirectional"))
    )
    (net (code "203") (name "unconnected-(IC24-Y4-Pad1)") (class "Default")
      (node (ref "IC24") (pin "1") (pinfunction "Y4_1") (pintype "bidirectional"))
    )
    (net (code "204") (name "unconnected-(IC24-Y5-Pad5)") (class "Default")
      (node (ref "IC24") (pin "5") (pinfunction "Y5_5") (pintype "bidirectional"))
    )
    (net (code "205") (name "unconnected-(IC24-Y6-Pad2)") (class "Default")
      (node (ref "IC24") (pin "2") (pinfunction "Y6_2") (pintype "bidirectional"))
    )
    (net (code "206") (name "unconnected-(IC24-Y7-Pad4)") (class "Default")
      (node (ref "IC24") (pin "4") (pinfunction "Y7_4") (pintype "bidirectional"))
    )
    (net (code "207") (name "unconnected-(IC26-Y2-Pad15)") (class "Default")
      (node (ref "IC26") (pin "15") (pinfunction "Y2_15") (pintype "bidirectional"))
    )
    (net (code "208") (name "unconnected-(IC26-Y3-Pad12)") (class "Default")
      (node (ref "IC26") (pin "12") (pinfunction "Y3_12") (pintype "bidirectional"))
    )
    (net (code "209") (name "unconnected-(IC26-Y4-Pad1)") (class "Default")
      (node (ref "IC26") (pin "1") (pinfunction "Y4_1") (pintype "bidirectional"))
    )
    (net (code "210") (name "unconnected-(IC26-Y5-Pad5)") (class "Default")
      (node (ref "IC26") (pin "5") (pinfunction "Y5_5") (pintype "bidirectional"))
    )
    (net (code "211") (name "unconnected-(IC26-Y6-Pad2)") (class "Default")
      (node (ref "IC26") (pin "2") (pinfunction "Y6_2") (pintype "bidirectional"))
    )
    (net (code "212") (name "unconnected-(IC26-Y7-Pad4)") (class "Default")
      (node (ref "IC26") (pin "4") (pinfunction "Y7_4") (pintype "bidirectional"))
    )
    (net (code "213") (name "unconnected-(IC28-Y2-Pad15)") (class "Default")
      (node (ref "IC28") (pin "15") (pinfunction "Y2_15") (pintype "bidirectional"))
    )
    (net (code "214") (name "unconnected-(IC28-Y3-Pad12)") (class "Default")
      (node (ref "IC28") (pin "12") (pinfunction "Y3_12") (pintype "bidirectional"))
    )
    (net (code "215") (name "unconnected-(IC28-Y4-Pad1)") (class "Default")
      (node (ref "IC28") (pin "1") (pinfunction "Y4_1") (pintype "bidirectional"))
    )
    (net (code "216") (name "unconnected-(IC28-Y5-Pad5)") (class "Default")
      (node (ref "IC28") (pin "5") (pinfunction "Y5_5") (pintype "bidirectional"))
    )
    (net (code "217") (name "unconnected-(IC28-Y6-Pad2)") (class "Default")
      (node (ref "IC28") (pin "2") (pinfunction "Y6_2") (pintype "bidirectional"))
    )
    (net (code "218") (name "unconnected-(IC28-Y7-Pad4)") (class "Default")
      (node (ref "IC28") (pin "4") (pinfunction "Y7_4") (pintype "bidirectional"))
    )
    (net (code "219") (name "unconnected-(IC30-NC-Pad1)") (class "Default")
      (node (ref "IC30") (pin "1") (pinfunction "NC_1") (pintype "no_connect"))
    )
    (net (code "220") (name "unconnected-(MOD1-GPIO_0-Pad5)") (class "Default")
      (node (ref "MOD1") (pin "5") (pinfunction "GPIO_0_5") (pintype "bidirectional"))
    )
    (net (code "221") (name "unconnected-(MOD1-GPIO_1-Pad6)") (class "Default")
      (node (ref "MOD1") (pin "6") (pinfunction "GPIO_1_6") (pintype "bidirectional"))
    )
    (net (code "222") (name "unconnected-(MOD1-GPIO_2-Pad7)") (class "Default")
      (node (ref "MOD1") (pin "7") (pinfunction "GPIO_2_7") (pintype "bidirectional"))
    )
  )
)
